# ArtFire.net
KiCad netlist of a schematic drawn in Altium Designer
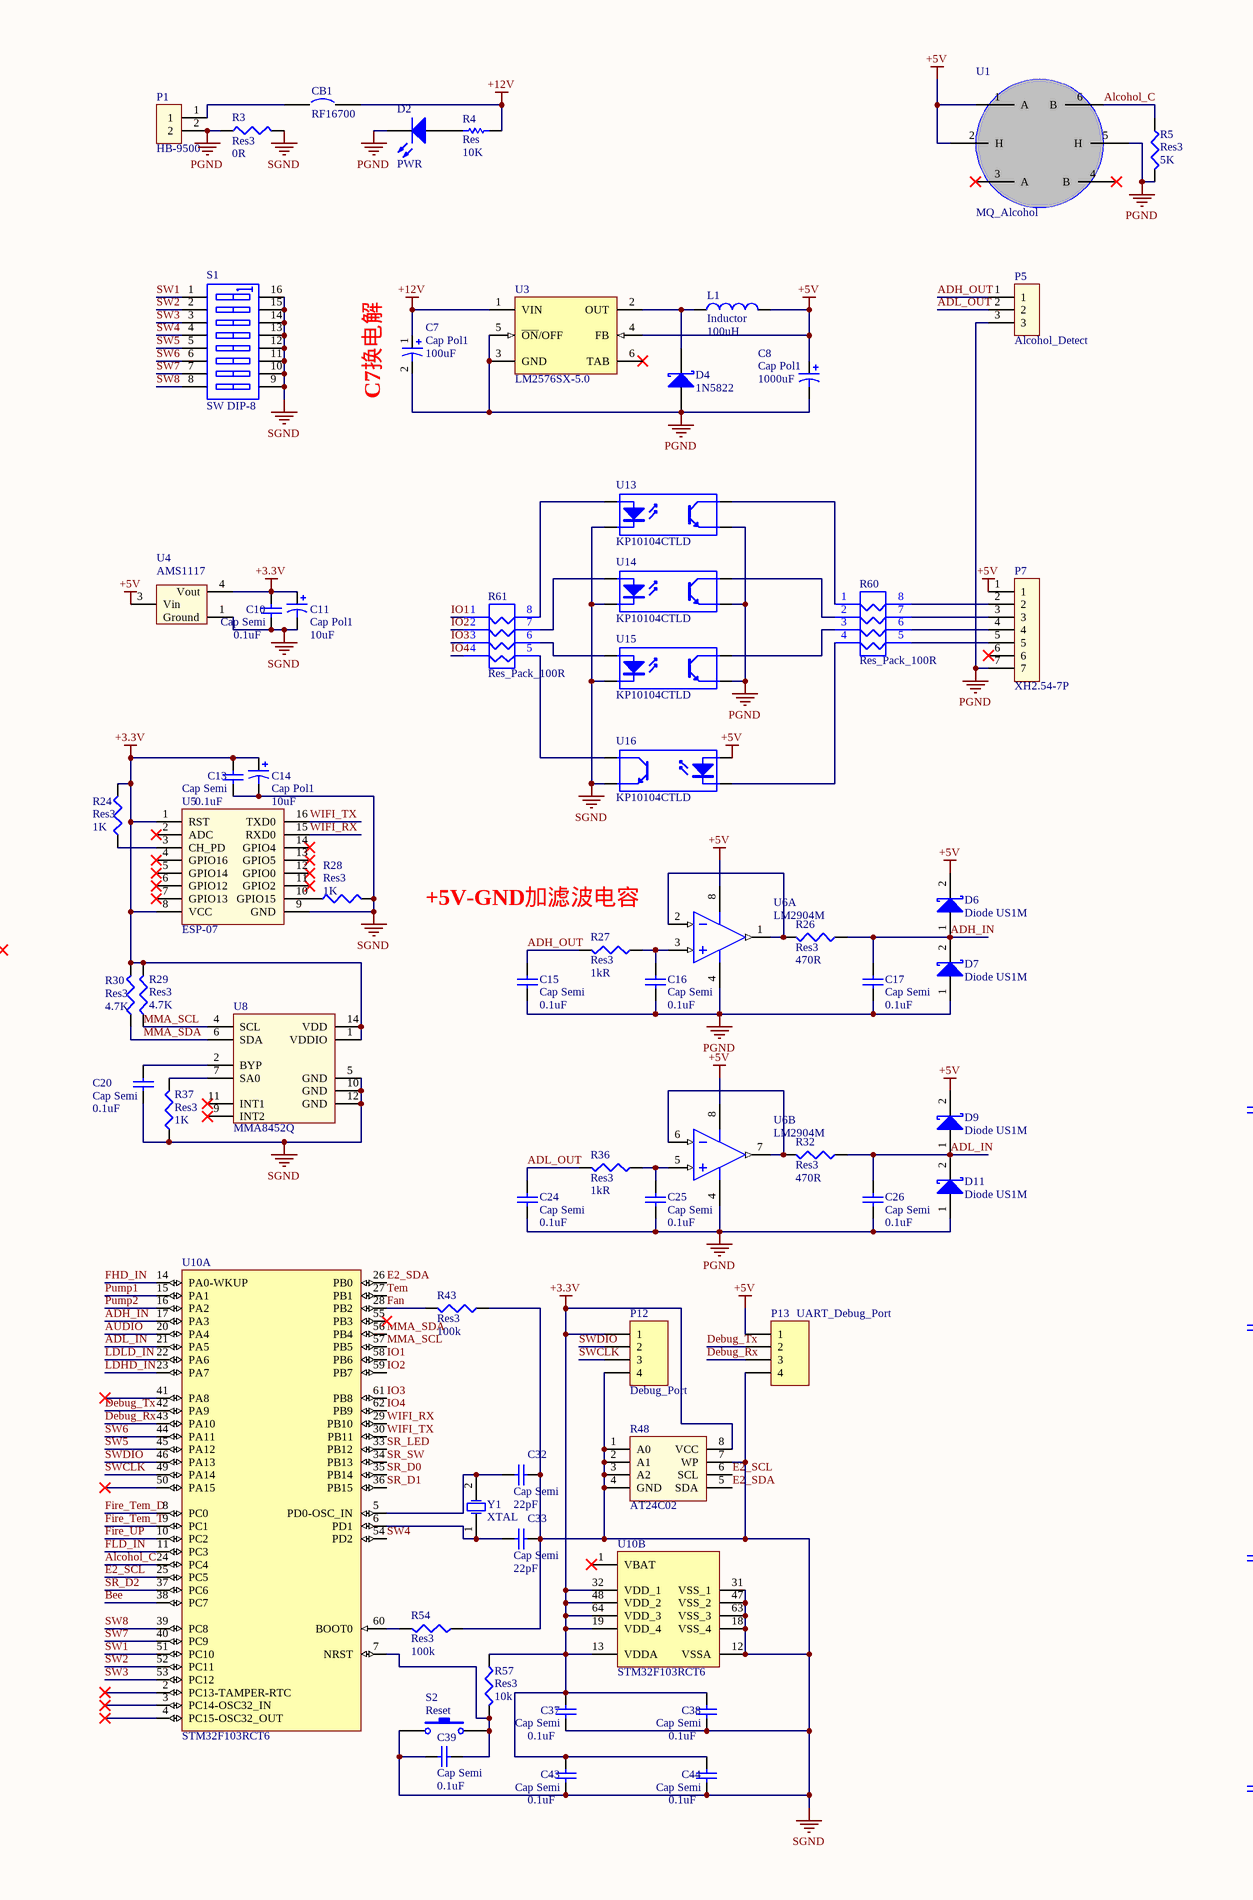
[diagram p0: ArtFire.SchDoc, left]
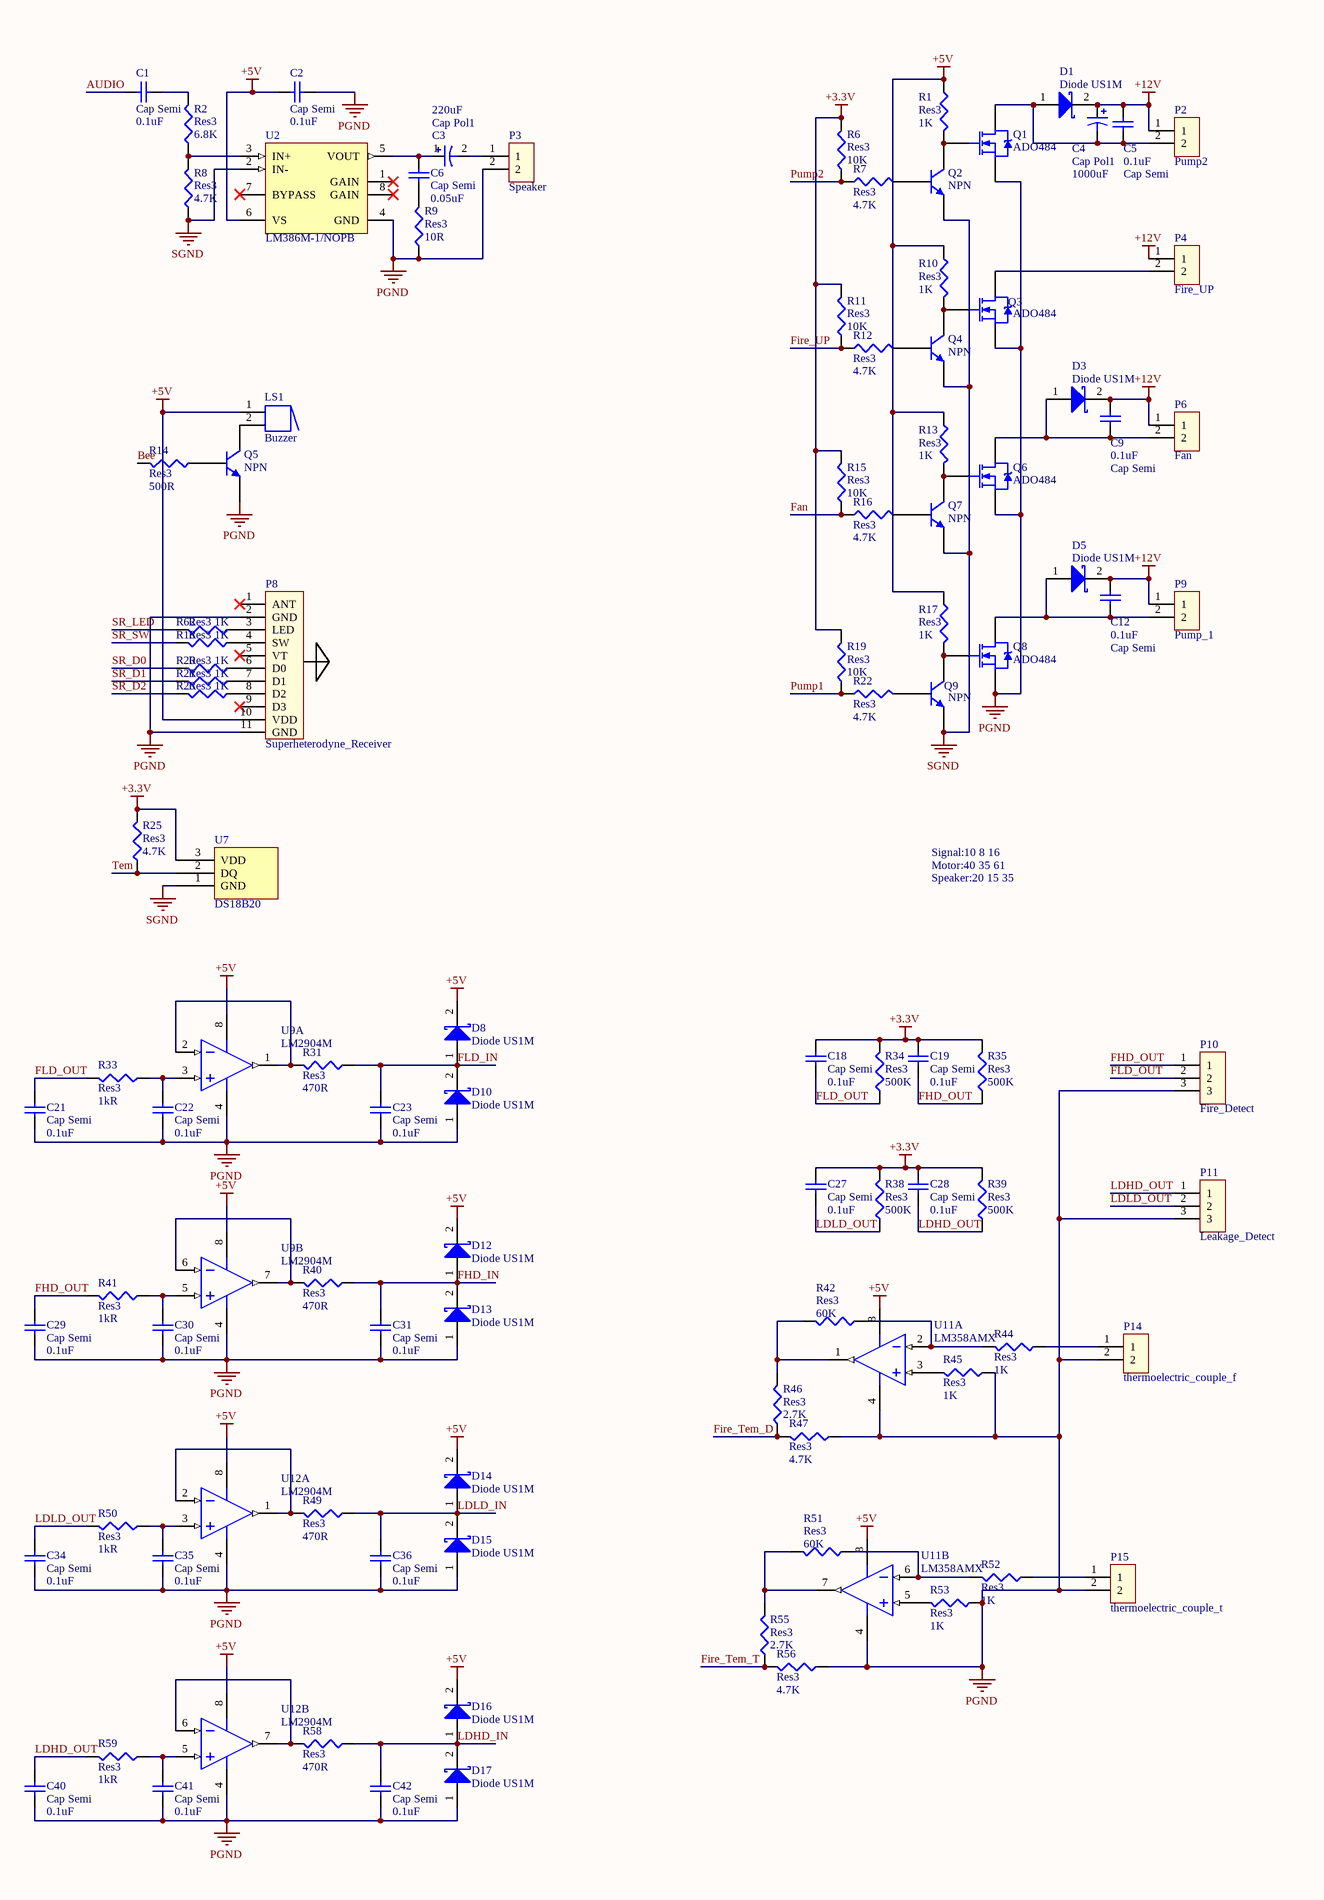
[diagram p1: ArtFire.SchDoc, right]

(export (version "E")
  (design (tool "Eeschema 10.0.6"))
  (components
    (comp (ref "C1")
      (value "Cap Semi")
      (footprint "6-0805_N")
      (description "Capacitor (Semiconductor SIM Model)")
      (fields (field (name "ALTIUM_VALUE") "0.1uF") (field (name "PUBLISHER") "Altium Limited"))
      (libsource (lib "Miscellaneous Devices") (part "Cap Semi"))
    )
    (comp (ref "C2")
      (value "Cap Semi")
      (footprint "6-0805_N")
      (description "Capacitor (Semiconductor SIM Model)")
      (fields (field (name "ALTIUM_VALUE") "0.1uF") (field (name "PUBLISHER") "Altium Limited"))
      (libsource (lib "Miscellaneous Devices") (part "Cap Semi"))
    )
    (comp (ref "C3")
      (value "Cap Pol1")
      (footprint "CAP_6.3*5.4MM")
      (description "Polarized Capacitor (Radial)")
      (fields (field (name "ALTIUM_VALUE") "220uF") (field (name "PUBLISHER") "Altium Limited"))
      (libsource (lib "Miscellaneous Devices") (part "Cap Pol1"))
    )
    (comp (ref "C4")
      (value "Cap Pol1")
      (footprint "CAP_10*10MM")
      (description "Polarized Capacitor (Radial)")
      (fields (field (name "ALTIUM_VALUE") "1000uF") (field (name "PUBLISHER") "Altium Limited"))
      (libsource (lib "") (part "Cap Pol1_1"))
    )
    (comp (ref "C5")
      (value "Cap Semi")
      (footprint "6-0805_N")
      (description "Capacitor (Semiconductor SIM Model)")
      (fields (field (name "ALTIUM_VALUE") "0.1uF") (field (name "PUBLISHER") "Altium Limited"))
      (libsource (lib "Miscellaneous Devices") (part "Cap Semi"))
    )
    (comp (ref "C6")
      (value "Cap Semi")
      (footprint "6-0805_N")
      (description "Capacitor (Semiconductor SIM Model)")
      (fields (field (name "ALTIUM_VALUE") "0.05uF") (field (name "PUBLISHER") "Altium Limited"))
      (libsource (lib "Miscellaneous Devices") (part "Cap Semi"))
    )
    (comp (ref "C7")
      (value "Cap Pol1")
      (footprint "6032")
      (description "Polarized Capacitor (Radial)")
      (fields (field (name "ALTIUM_VALUE") "100uF") (field (name "PUBLISHER") "Altium Limited"))
      (libsource (lib "Miscellaneous Devices") (part "Cap Pol1"))
    )
    (comp (ref "C8")
      (value "Cap Pol1")
      (footprint "CAP_10*10MM")
      (description "Polarized Capacitor (Radial)")
      (fields (field (name "ALTIUM_VALUE") "1000uF") (field (name "PUBLISHER") "Altium Limited"))
      (libsource (lib "") (part "Cap Pol1_1"))
    )
    (comp (ref "C9")
      (value "Cap Semi")
      (footprint "6-0805_N")
      (description "Capacitor (Semiconductor SIM Model)")
      (fields (field (name "ALTIUM_VALUE") "0.1uF") (field (name "PUBLISHER") "Altium Limited"))
      (libsource (lib "Miscellaneous Devices") (part "Cap Semi"))
    )
    (comp (ref "C10")
      (value "Cap Semi")
      (footprint "6-0805_N")
      (description "Capacitor (Semiconductor SIM Model)")
      (fields (field (name "ALTIUM_VALUE") "0.1uF") (field (name "PUBLISHER") "Altium Limited"))
      (libsource (lib "Miscellaneous Devices") (part "Cap Semi"))
    )
    (comp (ref "C11")
      (value "Cap Pol1")
      (footprint "Cap_5*4mm")
      (description "Polarized Capacitor (Radial)")
      (fields (field (name "ALTIUM_VALUE") "10uF") (field (name "PUBLISHER") "Altium Limited"))
      (libsource (lib "") (part "Cap Pol1_1"))
    )
    (comp (ref "C12")
      (value "Cap Semi")
      (footprint "6-0805_N")
      (description "Capacitor (Semiconductor SIM Model)")
      (fields (field (name "ALTIUM_VALUE") "0.1uF") (field (name "PUBLISHER") "Altium Limited"))
      (libsource (lib "Miscellaneous Devices") (part "Cap Semi"))
    )
    (comp (ref "C13")
      (value "Cap Semi")
      (footprint "6-0805_N")
      (description "Capacitor (Semiconductor SIM Model)")
      (fields (field (name "ALTIUM_VALUE") "0.1uF") (field (name "PUBLISHER") "Altium Limited"))
      (libsource (lib "Miscellaneous Devices") (part "Cap Semi"))
    )
    (comp (ref "C14")
      (value "Cap Pol1")
      (footprint "Cap_5*4mm")
      (description "Polarized Capacitor (Radial)")
      (fields (field (name "ALTIUM_VALUE") "10uF") (field (name "PUBLISHER") "Altium Limited"))
      (libsource (lib "") (part "Cap Pol1_1"))
    )
    (comp (ref "C15")
      (value "Cap Semi")
      (footprint "6-0805_N")
      (description "Capacitor (Semiconductor SIM Model)")
      (fields (field (name "ALTIUM_VALUE") "0.1uF") (field (name "PUBLISHER") "Altium Limited"))
      (libsource (lib "Miscellaneous Devices") (part "Cap Semi"))
    )
    (comp (ref "C16")
      (value "Cap Semi")
      (footprint "6-0805_N")
      (description "Capacitor (Semiconductor SIM Model)")
      (fields (field (name "ALTIUM_VALUE") "0.1uF") (field (name "PUBLISHER") "Altium Limited"))
      (libsource (lib "Miscellaneous Devices") (part "Cap Semi"))
    )
    (comp (ref "C17")
      (value "Cap Semi")
      (footprint "6-0805_N")
      (description "Capacitor (Semiconductor SIM Model)")
      (fields (field (name "ALTIUM_VALUE") "0.1uF") (field (name "PUBLISHER") "Altium Limited"))
      (libsource (lib "Miscellaneous Devices") (part "Cap Semi"))
    )
    (comp (ref "C18")
      (value "Cap Semi")
      (footprint "6-0805_N")
      (description "Capacitor (Semiconductor SIM Model)")
      (fields (field (name "ALTIUM_VALUE") "0.1uF") (field (name "PUBLISHER") "Altium Limited"))
      (libsource (lib "Miscellaneous Devices") (part "Cap Semi"))
    )
    (comp (ref "C19")
      (value "Cap Semi")
      (footprint "6-0805_N")
      (description "Capacitor (Semiconductor SIM Model)")
      (fields (field (name "ALTIUM_VALUE") "0.1uF") (field (name "PUBLISHER") "Altium Limited"))
      (libsource (lib "Miscellaneous Devices") (part "Cap Semi"))
    )
    (comp (ref "C20")
      (value "Cap Semi")
      (footprint "6-0805_N")
      (description "Capacitor (Semiconductor SIM Model)")
      (fields (field (name "ALTIUM_VALUE") "0.1uF") (field (name "PUBLISHER") "Altium Limited"))
      (libsource (lib "Miscellaneous Devices") (part "Cap Semi"))
    )
    (comp (ref "C21")
      (value "Cap Semi")
      (footprint "6-0805_N")
      (description "Capacitor (Semiconductor SIM Model)")
      (fields (field (name "ALTIUM_VALUE") "0.1uF") (field (name "PUBLISHER") "Altium Limited"))
      (libsource (lib "Miscellaneous Devices") (part "Cap Semi"))
    )
    (comp (ref "C22")
      (value "Cap Semi")
      (footprint "6-0805_N")
      (description "Capacitor (Semiconductor SIM Model)")
      (fields (field (name "ALTIUM_VALUE") "0.1uF") (field (name "PUBLISHER") "Altium Limited"))
      (libsource (lib "Miscellaneous Devices") (part "Cap Semi"))
    )
    (comp (ref "C23")
      (value "Cap Semi")
      (footprint "6-0805_N")
      (description "Capacitor (Semiconductor SIM Model)")
      (fields (field (name "ALTIUM_VALUE") "0.1uF") (field (name "PUBLISHER") "Altium Limited"))
      (libsource (lib "Miscellaneous Devices") (part "Cap Semi"))
    )
    (comp (ref "C24")
      (value "Cap Semi")
      (footprint "6-0805_N")
      (description "Capacitor (Semiconductor SIM Model)")
      (fields (field (name "ALTIUM_VALUE") "0.1uF") (field (name "PUBLISHER") "Altium Limited"))
      (libsource (lib "Miscellaneous Devices") (part "Cap Semi"))
    )
    (comp (ref "C25")
      (value "Cap Semi")
      (footprint "6-0805_N")
      (description "Capacitor (Semiconductor SIM Model)")
      (fields (field (name "ALTIUM_VALUE") "0.1uF") (field (name "PUBLISHER") "Altium Limited"))
      (libsource (lib "Miscellaneous Devices") (part "Cap Semi"))
    )
    (comp (ref "C26")
      (value "Cap Semi")
      (footprint "6-0805_N")
      (description "Capacitor (Semiconductor SIM Model)")
      (fields (field (name "ALTIUM_VALUE") "0.1uF") (field (name "PUBLISHER") "Altium Limited"))
      (libsource (lib "Miscellaneous Devices") (part "Cap Semi"))
    )
    (comp (ref "C27")
      (value "Cap Semi")
      (footprint "6-0805_N")
      (description "Capacitor (Semiconductor SIM Model)")
      (fields (field (name "ALTIUM_VALUE") "0.1uF") (field (name "PUBLISHER") "Altium Limited"))
      (libsource (lib "Miscellaneous Devices") (part "Cap Semi"))
    )
    (comp (ref "C28")
      (value "Cap Semi")
      (footprint "6-0805_N")
      (description "Capacitor (Semiconductor SIM Model)")
      (fields (field (name "ALTIUM_VALUE") "0.1uF") (field (name "PUBLISHER") "Altium Limited"))
      (libsource (lib "Miscellaneous Devices") (part "Cap Semi"))
    )
    (comp (ref "C29")
      (value "Cap Semi")
      (footprint "6-0805_N")
      (description "Capacitor (Semiconductor SIM Model)")
      (fields (field (name "ALTIUM_VALUE") "0.1uF") (field (name "PUBLISHER") "Altium Limited"))
      (libsource (lib "Miscellaneous Devices") (part "Cap Semi"))
    )
    (comp (ref "C30")
      (value "Cap Semi")
      (footprint "6-0805_N")
      (description "Capacitor (Semiconductor SIM Model)")
      (fields (field (name "ALTIUM_VALUE") "0.1uF") (field (name "PUBLISHER") "Altium Limited"))
      (libsource (lib "Miscellaneous Devices") (part "Cap Semi"))
    )
    (comp (ref "C31")
      (value "Cap Semi")
      (footprint "6-0805_N")
      (description "Capacitor (Semiconductor SIM Model)")
      (fields (field (name "ALTIUM_VALUE") "0.1uF") (field (name "PUBLISHER") "Altium Limited"))
      (libsource (lib "Miscellaneous Devices") (part "Cap Semi"))
    )
    (comp (ref "C32")
      (value "Cap Semi")
      (footprint "6-0805_N")
      (description "Capacitor (Semiconductor SIM Model)")
      (fields (field (name "ALTIUM_VALUE") "22pF") (field (name "PUBLISHER") "Altium Limited"))
      (libsource (lib "Miscellaneous Devices") (part "Cap Semi"))
    )
    (comp (ref "C33")
      (value "Cap Semi")
      (footprint "6-0805_N")
      (description "Capacitor (Semiconductor SIM Model)")
      (fields (field (name "ALTIUM_VALUE") "22pF") (field (name "PUBLISHER") "Altium Limited"))
      (libsource (lib "Miscellaneous Devices") (part "Cap Semi"))
    )
    (comp (ref "C34")
      (value "Cap Semi")
      (footprint "6-0805_N")
      (description "Capacitor (Semiconductor SIM Model)")
      (fields (field (name "ALTIUM_VALUE") "0.1uF") (field (name "PUBLISHER") "Altium Limited"))
      (libsource (lib "Miscellaneous Devices") (part "Cap Semi"))
    )
    (comp (ref "C35")
      (value "Cap Semi")
      (footprint "6-0805_N")
      (description "Capacitor (Semiconductor SIM Model)")
      (fields (field (name "ALTIUM_VALUE") "0.1uF") (field (name "PUBLISHER") "Altium Limited"))
      (libsource (lib "Miscellaneous Devices") (part "Cap Semi"))
    )
    (comp (ref "C36")
      (value "Cap Semi")
      (footprint "6-0805_N")
      (description "Capacitor (Semiconductor SIM Model)")
      (fields (field (name "ALTIUM_VALUE") "0.1uF") (field (name "PUBLISHER") "Altium Limited"))
      (libsource (lib "Miscellaneous Devices") (part "Cap Semi"))
    )
    (comp (ref "C37")
      (value "Cap Semi")
      (footprint "6-0805_N")
      (description "Capacitor (Semiconductor SIM Model)")
      (fields (field (name "ALTIUM_VALUE") "0.1uF") (field (name "PUBLISHER") "Altium Limited"))
      (libsource (lib "Miscellaneous Devices") (part "Cap Semi"))
    )
    (comp (ref "C38")
      (value "Cap Semi")
      (footprint "6-0805_N")
      (description "Capacitor (Semiconductor SIM Model)")
      (fields (field (name "ALTIUM_VALUE") "0.1uF") (field (name "PUBLISHER") "Altium Limited"))
      (libsource (lib "Miscellaneous Devices") (part "Cap Semi"))
    )
    (comp (ref "C39")
      (value "Cap Semi")
      (footprint "6-0805_N")
      (description "Capacitor (Semiconductor SIM Model)")
      (fields (field (name "ALTIUM_VALUE") "0.1uF") (field (name "PUBLISHER") "Altium Limited"))
      (libsource (lib "Miscellaneous Devices") (part "Cap Semi"))
    )
    (comp (ref "C40")
      (value "Cap Semi")
      (footprint "6-0805_N")
      (description "Capacitor (Semiconductor SIM Model)")
      (fields (field (name "ALTIUM_VALUE") "0.1uF") (field (name "PUBLISHER") "Altium Limited"))
      (libsource (lib "Miscellaneous Devices") (part "Cap Semi"))
    )
    (comp (ref "C41")
      (value "Cap Semi")
      (footprint "6-0805_N")
      (description "Capacitor (Semiconductor SIM Model)")
      (fields (field (name "ALTIUM_VALUE") "0.1uF") (field (name "PUBLISHER") "Altium Limited"))
      (libsource (lib "Miscellaneous Devices") (part "Cap Semi"))
    )
    (comp (ref "C42")
      (value "Cap Semi")
      (footprint "6-0805_N")
      (description "Capacitor (Semiconductor SIM Model)")
      (fields (field (name "ALTIUM_VALUE") "0.1uF") (field (name "PUBLISHER") "Altium Limited"))
      (libsource (lib "Miscellaneous Devices") (part "Cap Semi"))
    )
    (comp (ref "C43")
      (value "Cap Semi")
      (footprint "6-0805_N")
      (description "Capacitor (Semiconductor SIM Model)")
      (fields (field (name "ALTIUM_VALUE") "0.1uF") (field (name "PUBLISHER") "Altium Limited"))
      (libsource (lib "Miscellaneous Devices") (part "Cap Semi"))
    )
    (comp (ref "C44")
      (value "Cap Semi")
      (footprint "6-0805_N")
      (description "Capacitor (Semiconductor SIM Model)")
      (fields (field (name "ALTIUM_VALUE") "0.1uF") (field (name "PUBLISHER") "Altium Limited"))
      (libsource (lib "Miscellaneous Devices") (part "Cap Semi"))
    )
    (comp (ref "CB1")
      (value "RF16700")
      (footprint "SPST-2")
      (description "Circuit Breaker")
      (fields (field (name "PUBLISHER") "Altium Limited"))
      (libsource (lib "Miscellaneous Devices") (part "Circuit Breaker"))
    )
    (comp (ref "D1")
      (value "Diode US1M")
      (footprint "US1M")
      (description "Silicon RF Schottky Diode for Mixer Applications in the VHF/UHF Range")
      (fields (field (name "PUBLISHER") "Altium Limited"))
      (libsource (lib "Miscellaneous Devices") (part "Diode BAT17"))
    )
    (comp (ref "D2")
      (value "PWR")
      (footprint "6-0805_N")
      (description "Typical INFRARED GaAs LED")
      (fields (field (name "PUBLISHER") "Altium Limited"))
      (libsource (lib "Miscellaneous Devices") (part "LED0"))
    )
    (comp (ref "D3")
      (value "Diode US1M")
      (footprint "US1M")
      (description "Silicon RF Schottky Diode for Mixer Applications in the VHF/UHF Range")
      (fields (field (name "PUBLISHER") "Altium Limited"))
      (libsource (lib "Miscellaneous Devices") (part "Diode BAT17"))
    )
    (comp (ref "D4")
      (value "1N5822")
      (footprint "US1M")
      (description "Silicon RF Schottky Diode for Mixer Applications in the VHF/UHF Range")
      (fields (field (name "PUBLISHER") "Altium Limited"))
      (libsource (lib "") (part "Diode BAT17_1"))
    )
    (comp (ref "D5")
      (value "Diode US1M")
      (footprint "US1M")
      (description "Silicon RF Schottky Diode for Mixer Applications in the VHF/UHF Range")
      (fields (field (name "PUBLISHER") "Altium Limited"))
      (libsource (lib "Miscellaneous Devices") (part "Diode BAT17"))
    )
    (comp (ref "D6")
      (value "Diode US1M")
      (footprint "US1M")
      (description "Silicon RF Schottky Diode for Mixer Applications in the VHF/UHF Range")
      (fields (field (name "PUBLISHER") "Altium Limited"))
      (libsource (lib "Miscellaneous Devices") (part "Diode BAT17"))
    )
    (comp (ref "D7")
      (value "Diode US1M")
      (footprint "US1M")
      (description "Silicon RF Schottky Diode for Mixer Applications in the VHF/UHF Range")
      (fields (field (name "PUBLISHER") "Altium Limited"))
      (libsource (lib "Miscellaneous Devices") (part "Diode BAT17"))
    )
    (comp (ref "D8")
      (value "Diode US1M")
      (footprint "US1M")
      (description "Silicon RF Schottky Diode for Mixer Applications in the VHF/UHF Range")
      (fields (field (name "PUBLISHER") "Altium Limited"))
      (libsource (lib "Miscellaneous Devices") (part "Diode BAT17"))
    )
    (comp (ref "D9")
      (value "Diode US1M")
      (footprint "US1M")
      (description "Silicon RF Schottky Diode for Mixer Applications in the VHF/UHF Range")
      (fields (field (name "PUBLISHER") "Altium Limited"))
      (libsource (lib "Miscellaneous Devices") (part "Diode BAT17"))
    )
    (comp (ref "D10")
      (value "Diode US1M")
      (footprint "US1M")
      (description "Silicon RF Schottky Diode for Mixer Applications in the VHF/UHF Range")
      (fields (field (name "PUBLISHER") "Altium Limited"))
      (libsource (lib "Miscellaneous Devices") (part "Diode BAT17"))
    )
    (comp (ref "D11")
      (value "Diode US1M")
      (footprint "US1M")
      (description "Silicon RF Schottky Diode for Mixer Applications in the VHF/UHF Range")
      (fields (field (name "PUBLISHER") "Altium Limited"))
      (libsource (lib "Miscellaneous Devices") (part "Diode BAT17"))
    )
    (comp (ref "D12")
      (value "Diode US1M")
      (footprint "US1M")
      (description "Silicon RF Schottky Diode for Mixer Applications in the VHF/UHF Range")
      (fields (field (name "PUBLISHER") "Altium Limited"))
      (libsource (lib "Miscellaneous Devices") (part "Diode BAT17"))
    )
    (comp (ref "D13")
      (value "Diode US1M")
      (footprint "US1M")
      (description "Silicon RF Schottky Diode for Mixer Applications in the VHF/UHF Range")
      (fields (field (name "PUBLISHER") "Altium Limited"))
      (libsource (lib "Miscellaneous Devices") (part "Diode BAT17"))
    )
    (comp (ref "D14")
      (value "Diode US1M")
      (footprint "US1M")
      (description "Silicon RF Schottky Diode for Mixer Applications in the VHF/UHF Range")
      (fields (field (name "PUBLISHER") "Altium Limited"))
      (libsource (lib "Miscellaneous Devices") (part "Diode BAT17"))
    )
    (comp (ref "D15")
      (value "Diode US1M")
      (footprint "US1M")
      (description "Silicon RF Schottky Diode for Mixer Applications in the VHF/UHF Range")
      (fields (field (name "PUBLISHER") "Altium Limited"))
      (libsource (lib "Miscellaneous Devices") (part "Diode BAT17"))
    )
    (comp (ref "D16")
      (value "Diode US1M")
      (footprint "US1M")
      (description "Silicon RF Schottky Diode for Mixer Applications in the VHF/UHF Range")
      (fields (field (name "PUBLISHER") "Altium Limited"))
      (libsource (lib "Miscellaneous Devices") (part "Diode BAT17"))
    )
    (comp (ref "D17")
      (value "Diode US1M")
      (footprint "US1M")
      (description "Silicon RF Schottky Diode for Mixer Applications in the VHF/UHF Range")
      (fields (field (name "PUBLISHER") "Altium Limited"))
      (libsource (lib "Miscellaneous Devices") (part "Diode BAT17"))
    )
    (comp (ref "L1")
      (value "Inductor")
      (footprint "CDRH127")
      (fields (field (name "ALTIUM_VALUE") "100uH") (field (name "PUBLISHER") "Altium Limited"))
      (libsource (lib "Miscellaneous Devices") (part "Inductor"))
    )
    (comp (ref "LS1")
      (value "Buzzer")
      (footprint "BUZZER")
      (description "Magnetic Transducer Buzzer")
      (fields (field (name "PUBLISHER") "Altium Limited"))
      (libsource (lib "Miscellaneous Devices") (part "Buzzer"))
    )
    (comp (ref "P1")
      (value "HB-9500")
      (footprint "HB-9500")
      (description "High current connector")
      (libsource (lib "Simon'Library") (part "HB-9500"))
    )
    (comp (ref "P2") (value "Pump2") (footprint "CH3.96_2P") (libsource (lib "CH3.96") (part "CH3.96_2P")))
    (comp (ref "P3") (value "Speaker") (footprint "XH2.54-2P") (libsource (lib "XH2.54") (part "XH2.54-2P")))
    (comp (ref "P4") (value "Fire_UP") (footprint "KF7.62-2P") (libsource (lib "KF3.96") (part "KF3.96")))
    (comp (ref "P5")
      (value "Alcohol_Detect")
      (footprint "XH2.54-3P")
      (libsource (lib "XH2.54") (part "XH2.54-3P"))
    )
    (comp (ref "P6") (value "Fan") (footprint "XH2.54-2P") (libsource (lib "XH2.54") (part "XH2.54-2P")))
    (comp (ref "P7")
      (value "XH2.54-7P")
      (footprint "XH2.54-7P")
      (libsource (lib "XH2.54") (part "XH2.54-7P"))
    )
    (comp (ref "P8")
      (value "Superheterodyne_Receiver")
      (footprint "Sperheterodyne_Receiver")
      (libsource (lib "Simon'Library") (part "Superheterodyne_Receiver"))
    )
    (comp (ref "P9") (value "Pump_1") (footprint "CH3.96_2P") (libsource (lib "CH3.96") (part "CH3.96_2P")))
    (comp (ref "P10")
      (value "Fire_Detect")
      (footprint "CH3.96_3P")
      (libsource (lib "CH3.96") (part "CH3.96_3P"))
    )
    (comp (ref "P11")
      (value "Leakage_Detect")
      (footprint "XH2.54-3P")
      (libsource (lib "XH2.54") (part "XH2.54-3P"))
    )
    (comp (ref "P12")
      (value "Debug_Port")
      (footprint "HDR1X4")
      (description "Header, 4-Pin")
      (fields (field (name "PUBLISHER") "Altium Limited"))
      (libsource (lib "Miscellaneous Connectors") (part "Header 4"))
    )
    (comp (ref "P13")
      (value "UART_Debug_Port")
      (footprint "HDR1X4")
      (description "Header, 4-Pin")
      (fields (field (name "PUBLISHER") "Altium Limited"))
      (libsource (lib "Miscellaneous Connectors") (part "Header 4"))
    )
    (comp (ref "P14")
      (value "thermoelectric_couple_f")
      (footprint "KF7.62-2P")
      (libsource (lib "KF3.96") (part "KF3.96"))
    )
    (comp (ref "P15")
      (value "thermoelectric_couple_t")
      (footprint "KF7.62-2P")
      (libsource (lib "KF3.96") (part "KF3.96"))
    )
    (comp (ref "Q1")
      (value "ADO484")
      (footprint "DPAK_AOD484")
      (description "N-Channel Power MOSFET")
      (fields (field (name "PUBLISHER") "Altium Limited"))
      (libsource (lib "Miscellaneous Devices") (part "NMOS-2"))
    )
    (comp (ref "Q2")
      (value "NPN")
      (footprint "SOT-23_N")
      (description "NPN Bipolar Transistor")
      (fields (field (name "PUBLISHER") "Altium Limited"))
      (libsource (lib "Miscellaneous Devices") (part "NPN"))
    )
    (comp (ref "Q3")
      (value "ADO484")
      (footprint "DPAK_AOD484")
      (description "N-Channel Power MOSFET")
      (fields (field (name "PUBLISHER") "Altium Limited"))
      (libsource (lib "Miscellaneous Devices") (part "NMOS-2"))
    )
    (comp (ref "Q4")
      (value "NPN")
      (footprint "SOT-23_N")
      (description "NPN Bipolar Transistor")
      (fields (field (name "PUBLISHER") "Altium Limited"))
      (libsource (lib "Miscellaneous Devices") (part "NPN"))
    )
    (comp (ref "Q5")
      (value "NPN")
      (footprint "SOT-23_N")
      (description "NPN Bipolar Transistor")
      (fields (field (name "PUBLISHER") "Altium Limited"))
      (libsource (lib "Miscellaneous Devices") (part "NPN"))
    )
    (comp (ref "Q6")
      (value "ADO484")
      (footprint "DPAK_AOD484")
      (description "N-Channel Power MOSFET")
      (fields (field (name "PUBLISHER") "Altium Limited"))
      (libsource (lib "Miscellaneous Devices") (part "NMOS-2"))
    )
    (comp (ref "Q7")
      (value "NPN")
      (footprint "SOT-23_N")
      (description "NPN Bipolar Transistor")
      (fields (field (name "PUBLISHER") "Altium Limited"))
      (libsource (lib "Miscellaneous Devices") (part "NPN"))
    )
    (comp (ref "Q8")
      (value "ADO484")
      (footprint "DPAK_AOD484")
      (description "N-Channel Power MOSFET")
      (fields (field (name "PUBLISHER") "Altium Limited"))
      (libsource (lib "Miscellaneous Devices") (part "NMOS-2"))
    )
    (comp (ref "Q9")
      (value "NPN")
      (footprint "SOT-23_N")
      (description "NPN Bipolar Transistor")
      (fields (field (name "PUBLISHER") "Altium Limited"))
      (libsource (lib "Miscellaneous Devices") (part "NPN"))
    )
    (comp (ref "R1")
      (value "Res3")
      (footprint "6-0805_N")
      (description "Resistor")
      (fields (field (name "ALTIUM_VALUE") "1K") (field (name "PUBLISHER") "Altium Limited"))
      (libsource (lib "Miscellaneous Devices") (part "Res3"))
    )
    (comp (ref "R2")
      (value "Res3")
      (footprint "6-0805_N")
      (description "Resistor")
      (fields (field (name "ALTIUM_VALUE") "6.8K") (field (name "PUBLISHER") "Altium Limited"))
      (libsource (lib "Miscellaneous Devices") (part "Res3"))
    )
    (comp (ref "R3")
      (value "Res3")
      (footprint "6-0805_N")
      (description "Resistor")
      (fields (field (name "ALTIUM_VALUE") "0R") (field (name "PUBLISHER") "Altium Limited"))
      (libsource (lib "Miscellaneous Devices") (part "Res3"))
    )
    (comp (ref "R4")
      (value "Res")
      (footprint "6-0805_N")
      (description "Resistor")
      (fields (field (name "ALTIUM_VALUE") "10K") (field (name "PUBLISHER") "Altium Limited"))
      (libsource (lib "Miscellaneous Devices") (part "Res1"))
    )
    (comp (ref "R5")
      (value "Res3")
      (footprint "6-0805_N")
      (description "Resistor")
      (fields (field (name "ALTIUM_VALUE") "5K") (field (name "PUBLISHER") "Altium Limited"))
      (libsource (lib "Miscellaneous Devices") (part "Res3"))
    )
    (comp (ref "R6")
      (value "Res3")
      (footprint "6-0805_N")
      (description "Resistor")
      (fields (field (name "ALTIUM_VALUE") "10K") (field (name "PUBLISHER") "Altium Limited"))
      (libsource (lib "Miscellaneous Devices") (part "Res3"))
    )
    (comp (ref "R7")
      (value "Res3")
      (footprint "6-0805_N")
      (description "Resistor")
      (fields (field (name "ALTIUM_VALUE") "4.7K") (field (name "PUBLISHER") "Altium Limited"))
      (libsource (lib "Miscellaneous Devices") (part "Res3"))
    )
    (comp (ref "R8")
      (value "Res3")
      (footprint "6-0805_N")
      (description "Resistor")
      (fields (field (name "ALTIUM_VALUE") "4.7K") (field (name "PUBLISHER") "Altium Limited"))
      (libsource (lib "Miscellaneous Devices") (part "Res3"))
    )
    (comp (ref "R9")
      (value "Res3")
      (footprint "6-0805_N")
      (description "Resistor")
      (fields (field (name "ALTIUM_VALUE") "10R") (field (name "PUBLISHER") "Altium Limited"))
      (libsource (lib "Miscellaneous Devices") (part "Res3"))
    )
    (comp (ref "R10")
      (value "Res3")
      (footprint "6-0805_N")
      (description "Resistor")
      (fields (field (name "ALTIUM_VALUE") "1K") (field (name "PUBLISHER") "Altium Limited"))
      (libsource (lib "Miscellaneous Devices") (part "Res3"))
    )
    (comp (ref "R11")
      (value "Res3")
      (footprint "6-0805_N")
      (description "Resistor")
      (fields (field (name "ALTIUM_VALUE") "10K") (field (name "PUBLISHER") "Altium Limited"))
      (libsource (lib "Miscellaneous Devices") (part "Res3"))
    )
    (comp (ref "R12")
      (value "Res3")
      (footprint "6-0805_N")
      (description "Resistor")
      (fields (field (name "ALTIUM_VALUE") "4.7K") (field (name "PUBLISHER") "Altium Limited"))
      (libsource (lib "Miscellaneous Devices") (part "Res3"))
    )
    (comp (ref "R13")
      (value "Res3")
      (footprint "6-0805_N")
      (description "Resistor")
      (fields (field (name "ALTIUM_VALUE") "1K") (field (name "PUBLISHER") "Altium Limited"))
      (libsource (lib "Miscellaneous Devices") (part "Res3"))
    )
    (comp (ref "R14")
      (value "Res3")
      (footprint "6-0805_N")
      (description "Resistor")
      (fields (field (name "ALTIUM_VALUE") "500R") (field (name "PUBLISHER") "Altium Limited"))
      (libsource (lib "Miscellaneous Devices") (part "Res3"))
    )
    (comp (ref "R15")
      (value "Res3")
      (footprint "6-0805_N")
      (description "Resistor")
      (fields (field (name "ALTIUM_VALUE") "10K") (field (name "PUBLISHER") "Altium Limited"))
      (libsource (lib "Miscellaneous Devices") (part "Res3"))
    )
    (comp (ref "R16")
      (value "Res3")
      (footprint "6-0805_N")
      (description "Resistor")
      (fields (field (name "ALTIUM_VALUE") "4.7K") (field (name "PUBLISHER") "Altium Limited"))
      (libsource (lib "Miscellaneous Devices") (part "Res3"))
    )
    (comp (ref "R17")
      (value "Res3")
      (footprint "6-0805_N")
      (description "Resistor")
      (fields (field (name "ALTIUM_VALUE") "1K") (field (name "PUBLISHER") "Altium Limited"))
      (libsource (lib "Miscellaneous Devices") (part "Res3"))
    )
    (comp (ref "R18")
      (value "Res3")
      (footprint "6-0805_N")
      (description "Resistor")
      (fields (field (name "ALTIUM_VALUE") "1K") (field (name "PUBLISHER") "Altium Limited"))
      (libsource (lib "Miscellaneous Devices") (part "Res3"))
    )
    (comp (ref "R19")
      (value "Res3")
      (footprint "6-0805_N")
      (description "Resistor")
      (fields (field (name "ALTIUM_VALUE") "10K") (field (name "PUBLISHER") "Altium Limited"))
      (libsource (lib "Miscellaneous Devices") (part "Res3"))
    )
    (comp (ref "R20")
      (value "Res3")
      (footprint "6-0805_N")
      (description "Resistor")
      (fields (field (name "ALTIUM_VALUE") "1K") (field (name "PUBLISHER") "Altium Limited"))
      (libsource (lib "Miscellaneous Devices") (part "Res3"))
    )
    (comp (ref "R21")
      (value "Res3")
      (footprint "6-0805_N")
      (description "Resistor")
      (fields (field (name "ALTIUM_VALUE") "1K") (field (name "PUBLISHER") "Altium Limited"))
      (libsource (lib "Miscellaneous Devices") (part "Res3"))
    )
    (comp (ref "R22")
      (value "Res3")
      (footprint "6-0805_N")
      (description "Resistor")
      (fields (field (name "ALTIUM_VALUE") "4.7K") (field (name "PUBLISHER") "Altium Limited"))
      (libsource (lib "Miscellaneous Devices") (part "Res3"))
    )
    (comp (ref "R23")
      (value "Res3")
      (footprint "6-0805_N")
      (description "Resistor")
      (fields (field (name "ALTIUM_VALUE") "1K") (field (name "PUBLISHER") "Altium Limited"))
      (libsource (lib "Miscellaneous Devices") (part "Res3"))
    )
    (comp (ref "R24")
      (value "Res3")
      (footprint "6-0805_N")
      (description "Resistor")
      (fields (field (name "ALTIUM_VALUE") "1K") (field (name "PUBLISHER") "Altium Limited"))
      (libsource (lib "Miscellaneous Devices") (part "Res3"))
    )
    (comp (ref "R25")
      (value "Res3")
      (footprint "6-0805_N")
      (description "Resistor")
      (fields (field (name "ALTIUM_VALUE") "4.7K") (field (name "PUBLISHER") "Altium Limited"))
      (libsource (lib "Miscellaneous Devices") (part "Res3"))
    )
    (comp (ref "R26")
      (value "Res3")
      (footprint "6-0805_N")
      (description "Resistor")
      (fields (field (name "ALTIUM_VALUE") "470R") (field (name "PUBLISHER") "Altium Limited"))
      (libsource (lib "Miscellaneous Devices") (part "Res3"))
    )
    (comp (ref "R27")
      (value "Res3")
      (footprint "6-0805_N")
      (description "Resistor")
      (fields (field (name "ALTIUM_VALUE") "1kR") (field (name "PUBLISHER") "Altium Limited"))
      (libsource (lib "Miscellaneous Devices") (part "Res3"))
    )
    (comp (ref "R28")
      (value "Res3")
      (footprint "6-0805_N")
      (description "Resistor")
      (fields (field (name "ALTIUM_VALUE") "1K") (field (name "PUBLISHER") "Altium Limited"))
      (libsource (lib "Miscellaneous Devices") (part "Res3"))
    )
    (comp (ref "R29")
      (value "Res3")
      (footprint "6-0805_N")
      (description "Resistor")
      (fields (field (name "ALTIUM_VALUE") "4.7K") (field (name "PUBLISHER") "Altium Limited"))
      (libsource (lib "Miscellaneous Devices") (part "Res3"))
    )
    (comp (ref "R30")
      (value "Res3")
      (footprint "6-0805_N")
      (description "Resistor")
      (fields (field (name "ALTIUM_VALUE") "4.7K") (field (name "PUBLISHER") "Altium Limited"))
      (libsource (lib "Miscellaneous Devices") (part "Res3"))
    )
    (comp (ref "R31")
      (value "Res3")
      (footprint "6-0805_N")
      (description "Resistor")
      (fields (field (name "ALTIUM_VALUE") "470R") (field (name "PUBLISHER") "Altium Limited"))
      (libsource (lib "Miscellaneous Devices") (part "Res3"))
    )
    (comp (ref "R32")
      (value "Res3")
      (footprint "6-0805_N")
      (description "Resistor")
      (fields (field (name "ALTIUM_VALUE") "470R") (field (name "PUBLISHER") "Altium Limited"))
      (libsource (lib "Miscellaneous Devices") (part "Res3"))
    )
    (comp (ref "R33")
      (value "Res3")
      (footprint "6-0805_N")
      (description "Resistor")
      (fields (field (name "ALTIUM_VALUE") "1kR") (field (name "PUBLISHER") "Altium Limited"))
      (libsource (lib "Miscellaneous Devices") (part "Res3"))
    )
    (comp (ref "R34")
      (value "Res3")
      (footprint "6-0805_N")
      (description "Resistor")
      (fields (field (name "ALTIUM_VALUE") "500K") (field (name "PUBLISHER") "Altium Limited"))
      (libsource (lib "Miscellaneous Devices") (part "Res3"))
    )
    (comp (ref "R35")
      (value "Res3")
      (footprint "6-0805_N")
      (description "Resistor")
      (fields (field (name "ALTIUM_VALUE") "500K") (field (name "PUBLISHER") "Altium Limited"))
      (libsource (lib "Miscellaneous Devices") (part "Res3"))
    )
    (comp (ref "R36")
      (value "Res3")
      (footprint "6-0805_N")
      (description "Resistor")
      (fields (field (name "ALTIUM_VALUE") "1kR") (field (name "PUBLISHER") "Altium Limited"))
      (libsource (lib "Miscellaneous Devices") (part "Res3"))
    )
    (comp (ref "R37")
      (value "Res3")
      (footprint "6-0805_N")
      (description "Resistor")
      (fields (field (name "ALTIUM_VALUE") "1K") (field (name "PUBLISHER") "Altium Limited"))
      (libsource (lib "Miscellaneous Devices") (part "Res3"))
    )
    (comp (ref "R38")
      (value "Res3")
      (footprint "6-0805_N")
      (description "Resistor")
      (fields (field (name "ALTIUM_VALUE") "500K") (field (name "PUBLISHER") "Altium Limited"))
      (libsource (lib "Miscellaneous Devices") (part "Res3"))
    )
    (comp (ref "R39")
      (value "Res3")
      (footprint "6-0805_N")
      (description "Resistor")
      (fields (field (name "ALTIUM_VALUE") "500K") (field (name "PUBLISHER") "Altium Limited"))
      (libsource (lib "Miscellaneous Devices") (part "Res3"))
    )
    (comp (ref "R40")
      (value "Res3")
      (footprint "6-0805_N")
      (description "Resistor")
      (fields (field (name "ALTIUM_VALUE") "470R") (field (name "PUBLISHER") "Altium Limited"))
      (libsource (lib "Miscellaneous Devices") (part "Res3"))
    )
    (comp (ref "R41")
      (value "Res3")
      (footprint "6-0805_N")
      (description "Resistor")
      (fields (field (name "ALTIUM_VALUE") "1kR") (field (name "PUBLISHER") "Altium Limited"))
      (libsource (lib "Miscellaneous Devices") (part "Res3"))
    )
    (comp (ref "R42")
      (value "Res3")
      (footprint "6-0805_N")
      (description "Resistor")
      (fields (field (name "ALTIUM_VALUE") "60K") (field (name "PUBLISHER") "Altium Limited"))
      (libsource (lib "Miscellaneous Devices") (part "Res3"))
    )
    (comp (ref "R43")
      (value "Res3")
      (footprint "6-0805_N")
      (description "Resistor")
      (fields (field (name "ALTIUM_VALUE") "100k") (field (name "PUBLISHER") "Altium Limited"))
      (libsource (lib "Miscellaneous Devices") (part "Res3"))
    )
    (comp (ref "R44")
      (value "Res3")
      (footprint "6-0805_N")
      (description "Resistor")
      (fields (field (name "ALTIUM_VALUE") "1K") (field (name "PUBLISHER") "Altium Limited"))
      (libsource (lib "Miscellaneous Devices") (part "Res3"))
    )
    (comp (ref "R45")
      (value "Res3")
      (footprint "6-0805_N")
      (description "Resistor")
      (fields (field (name "ALTIUM_VALUE") "1K") (field (name "PUBLISHER") "Altium Limited"))
      (libsource (lib "Miscellaneous Devices") (part "Res3"))
    )
    (comp (ref "R46")
      (value "Res3")
      (footprint "6-0805_N")
      (description "Resistor")
      (fields (field (name "ALTIUM_VALUE") "2.7K") (field (name "PUBLISHER") "Altium Limited"))
      (libsource (lib "Miscellaneous Devices") (part "Res3"))
    )
    (comp (ref "R47")
      (value "Res3")
      (footprint "6-0805_N")
      (description "Resistor")
      (fields (field (name "ALTIUM_VALUE") "4.7K") (field (name "PUBLISHER") "Altium Limited"))
      (libsource (lib "Miscellaneous Devices") (part "Res3"))
    )
    (comp (ref "R48")
      (value "AT24C02")
      (footprint "SOP8_TDA2822")
      (libsource (lib "Simon'Library") (part "AT24C02"))
    )
    (comp (ref "R49")
      (value "Res3")
      (footprint "6-0805_N")
      (description "Resistor")
      (fields (field (name "ALTIUM_VALUE") "470R") (field (name "PUBLISHER") "Altium Limited"))
      (libsource (lib "Miscellaneous Devices") (part "Res3"))
    )
    (comp (ref "R50")
      (value "Res3")
      (footprint "6-0805_N")
      (description "Resistor")
      (fields (field (name "ALTIUM_VALUE") "1kR") (field (name "PUBLISHER") "Altium Limited"))
      (libsource (lib "Miscellaneous Devices") (part "Res3"))
    )
    (comp (ref "R51")
      (value "Res3")
      (footprint "6-0805_N")
      (description "Resistor")
      (fields (field (name "ALTIUM_VALUE") "60K") (field (name "PUBLISHER") "Altium Limited"))
      (libsource (lib "Miscellaneous Devices") (part "Res3"))
    )
    (comp (ref "R52")
      (value "Res3")
      (footprint "6-0805_N")
      (description "Resistor")
      (fields (field (name "ALTIUM_VALUE") "1K") (field (name "PUBLISHER") "Altium Limited"))
      (libsource (lib "Miscellaneous Devices") (part "Res3"))
    )
    (comp (ref "R53")
      (value "Res3")
      (footprint "6-0805_N")
      (description "Resistor")
      (fields (field (name "ALTIUM_VALUE") "1K") (field (name "PUBLISHER") "Altium Limited"))
      (libsource (lib "Miscellaneous Devices") (part "Res3"))
    )
    (comp (ref "R54")
      (value "Res3")
      (footprint "6-0805_N")
      (description "Resistor")
      (fields (field (name "ALTIUM_VALUE") "100k") (field (name "PUBLISHER") "Altium Limited"))
      (libsource (lib "Miscellaneous Devices") (part "Res3"))
    )
    (comp (ref "R55")
      (value "Res3")
      (footprint "6-0805_N")
      (description "Resistor")
      (fields (field (name "ALTIUM_VALUE") "2.7K") (field (name "PUBLISHER") "Altium Limited"))
      (libsource (lib "Miscellaneous Devices") (part "Res3"))
    )
    (comp (ref "R56")
      (value "Res3")
      (footprint "6-0805_N")
      (description "Resistor")
      (fields (field (name "ALTIUM_VALUE") "4.7K") (field (name "PUBLISHER") "Altium Limited"))
      (libsource (lib "Miscellaneous Devices") (part "Res3"))
    )
    (comp (ref "R57")
      (value "Res3")
      (footprint "6-0805_N")
      (description "Resistor")
      (fields (field (name "ALTIUM_VALUE") "10k") (field (name "PUBLISHER") "Altium Limited"))
      (libsource (lib "Miscellaneous Devices") (part "Res3"))
    )
    (comp (ref "R58")
      (value "Res3")
      (footprint "6-0805_N")
      (description "Resistor")
      (fields (field (name "ALTIUM_VALUE") "470R") (field (name "PUBLISHER") "Altium Limited"))
      (libsource (lib "Miscellaneous Devices") (part "Res3"))
    )
    (comp (ref "R59")
      (value "Res3")
      (footprint "6-0805_N")
      (description "Resistor")
      (fields (field (name "ALTIUM_VALUE") "1kR") (field (name "PUBLISHER") "Altium Limited"))
      (libsource (lib "Miscellaneous Devices") (part "Res3"))
    )
    (comp (ref "R60")
      (value "Res_Pack_100R")
      (footprint "Res_Pack_0603")
      (description "Res_Pack_4")
      (libsource (lib "Simon'Library") (part "Res_Pack_4"))
    )
    (comp (ref "R61")
      (value "Res_Pack_100R")
      (footprint "Res_Pack_0603")
      (description "Res_Pack_4")
      (libsource (lib "Simon'Library") (part "Res_Pack_4"))
    )
    (comp (ref "R62")
      (value "Res3")
      (footprint "6-0805_N")
      (description "Resistor")
      (fields (field (name "ALTIUM_VALUE") "1K") (field (name "PUBLISHER") "Altium Limited"))
      (libsource (lib "Miscellaneous Devices") (part "Res3"))
    )
    (comp (ref "S1")
      (value "SW DIP-8")
      (footprint "DHN(F)_8Pin")
      (description "DIP Switch, 8 Position, SPST")
      (fields (field (name "PUBLISHER") "Altium Limited"))
      (libsource (lib "Miscellaneous Devices") (part "SW DIP-8"))
    )
    (comp (ref "S2")
      (value "Reset")
      (footprint "SWP_PB_6.5mm")
      (description "Switch")
      (fields (field (name "PUBLISHER") "Altium Limited"))
      (libsource (lib "Miscellaneous Devices") (part "SW-PB"))
    )
    (comp (ref "U1") (value "MQ_Alcohol") (footprint "MQ") (libsource (lib "Simon'Library") (part "MQ")))
    (comp (ref "U2")
      (value "LM386M-1/NOPB")
      (footprint "M08A_M")
      (description "Low Voltage Audio Power Amplifier, 8-pin Narrow SOIC, Pb-Free")
      (fields (field (name "MANUFACTURER") "National Semiconductor"))
      (libsource (lib "Altium Content Vault") (part "AMP-APA-LM386-8"))
    )
    (comp (ref "U3")
      (value "LM2576SX-5.0")
      (footprint "TS5B_L")
      (description "SIMPLE SWITCHER® 3A Step-Down Voltage Regulator, 5-pin TO-263")
      (fields (field (name "MANUFACTURER") "National Semiconductor"))
      (libsource (lib "Altium Content Vault") (part "PM-REG-LM2575HVS-12"))
    )
    (comp (ref "U4")
      (value "AMS1117")
      (footprint "SOT223_N")
      (libsource (lib "Simon'Library") (part "AMS1117"))
    )
    (comp (ref "U5")
      (value "ESP-07")
      (footprint "ESP-07_Wifi")
      (libsource (lib "Simon'Library") (part "ESP-07_Wifi"))
    )
    (comp (ref "U6")
      (value "LM2904M")
      (footprint "D0008A_M")
      (description "Low Power Dual Operational Amplifier, 8-pin Narrow SOIC")
      (fields (field (name "MANUFACTURER") "Texas Instruments"))
      (libsource (lib "Altium Content Vault") (part "AMP-OPA-LM158-8"))
    )
    (comp (ref "U7")
      (value "DS18B20")
      (footprint "TO-92A")
      (libsource (lib "Simon'Library") (part "DS18B20"))
    )
    (comp (ref "U8")
      (value "MMA8452Q")
      (footprint "QFN-16")
      (libsource (lib "Simon'Library") (part "MMA8452Q"))
    )
    (comp (ref "U9")
      (value "LM2904M")
      (footprint "D0008A_M")
      (description "Low Power Dual Operational Amplifier, 8-pin Narrow SOIC")
      (fields (field (name "MANUFACTURER") "Texas Instruments"))
      (libsource (lib "Altium Content Vault") (part "AMP-OPA-LM158-8"))
    )
    (comp (ref "U10")
      (value "STM32F103RCT6")
      (footprint "LQFP64_L")
      (libsource (lib "Altium Content Vault") (part "MC-ARM-STM32F101-SQ64"))
    )
    (comp (ref "U11")
      (value "LM358AMX")
      (footprint "M08A_M")
      (description "Low Power Dual Operational Amplifier, 8-pin Narrow SOIC")
      (fields (field (name "MANUFACTURER") "National Semiconductor"))
      (libsource (lib "Altium Content Vault") (part "AMP-OPA-LM158-8"))
    )
    (comp (ref "U12")
      (value "LM2904M")
      (footprint "D0008A_M")
      (description "Low Power Dual Operational Amplifier, 8-pin Narrow SOIC")
      (fields (field (name "MANUFACTURER") "Texas Instruments"))
      (libsource (lib "Altium Content Vault") (part "AMP-OPA-LM158-8"))
    )
    (comp (ref "U13")
      (value "KP10104CTLD")
      (footprint "KP10104CTLD")
      (description "4-Pin Phototransistor Optocoupler")
      (fields (field (name "PUBLISHER") "Altium Limited"))
      (libsource (lib "Miscellaneous Devices") (part "Optoisolator1"))
    )
    (comp (ref "U14")
      (value "KP10104CTLD")
      (footprint "KP10104CTLD")
      (description "4-Pin Phototransistor Optocoupler")
      (fields (field (name "PUBLISHER") "Altium Limited"))
      (libsource (lib "Miscellaneous Devices") (part "Optoisolator1"))
    )
    (comp (ref "U15")
      (value "KP10104CTLD")
      (footprint "KP10104CTLD")
      (description "4-Pin Phototransistor Optocoupler")
      (fields (field (name "PUBLISHER") "Altium Limited"))
      (libsource (lib "Miscellaneous Devices") (part "Optoisolator1"))
    )
    (comp (ref "U16")
      (value "KP10104CTLD")
      (footprint "KP10104CTLD")
      (description "4-Pin Phototransistor Optocoupler")
      (fields (field (name "PUBLISHER") "Altium Limited"))
      (libsource (lib "Miscellaneous Devices") (part "Optoisolator1"))
    )
    (comp (ref "Y1")
      (value "XTAL")
      (footprint "OSC_5032_2Pin")
      (description "Crystal Oscillator")
      (fields (field (name "PUBLISHER") "Altium Limited"))
      (libsource (lib "Miscellaneous Devices") (part "XTAL"))
    )
  )
  (nets
    (net (code "1") (name "+3.3V") (class "Default")
      (node (ref "C10") (pin "1") (pinfunction "1_1") (pintype "passive"))
      (node (ref "C11") (pin "1") (pinfunction "1_1") (pintype "passive"))
      (node (ref "C13") (pin "1") (pinfunction "1_1") (pintype "passive"))
      (node (ref "C14") (pin "1") (pinfunction "1_1") (pintype "passive"))
      (node (ref "C18") (pin "2") (pinfunction "2_2") (pintype "passive"))
      (node (ref "C19") (pin "2") (pinfunction "2_2") (pintype "passive"))
      (node (ref "C27") (pin "2") (pinfunction "2_2") (pintype "passive"))
      (node (ref "C28") (pin "2") (pinfunction "2_2") (pintype "passive"))
      (node (ref "C37") (pin "1") (pinfunction "1_1") (pintype "passive"))
      (node (ref "C38") (pin "1") (pinfunction "1_1") (pintype "passive"))
      (node (ref "C43") (pin "1") (pinfunction "1_1") (pintype "passive"))
      (node (ref "C44") (pin "1") (pinfunction "1_1") (pintype "passive"))
      (node (ref "P12") (pin "1") (pinfunction "1_1") (pintype "passive"))
      (node (ref "R11") (pin "2") (pinfunction "2_2") (pintype "passive"))
      (node (ref "R15") (pin "2") (pinfunction "2_2") (pintype "passive"))
      (node (ref "R19") (pin "2") (pinfunction "2_2") (pintype "passive"))
      (node (ref "R24") (pin "2") (pinfunction "2_2") (pintype "passive"))
      (node (ref "R25") (pin "2") (pinfunction "2_2") (pintype "passive"))
      (node (ref "R29") (pin "2") (pinfunction "2_2") (pintype "passive"))
      (node (ref "R30") (pin "2") (pinfunction "2_2") (pintype "passive"))
      (node (ref "R34") (pin "2") (pinfunction "2_2") (pintype "passive"))
      (node (ref "R35") (pin "2") (pinfunction "2_2") (pintype "passive"))
      (node (ref "R38") (pin "2") (pinfunction "2_2") (pintype "passive"))
      (node (ref "R39") (pin "2") (pinfunction "2_2") (pintype "passive"))
      (node (ref "R48") (pin "8") (pinfunction "VCC_8") (pintype "passive"))
      (node (ref "R57") (pin "1") (pinfunction "1_1") (pintype "passive"))
      (node (ref "R6") (pin "2") (pinfunction "2_2") (pintype "passive"))
      (node (ref "U10") (pin "13") (pinfunction "VDDA_13") (pintype "power_in"))
      (node (ref "U10") (pin "19") (pinfunction "VDD_4_19") (pintype "power_in"))
      (node (ref "U10") (pin "32") (pinfunction "VDD_1_32") (pintype "power_in"))
      (node (ref "U10") (pin "48") (pinfunction "VDD_2_48") (pintype "power_in"))
      (node (ref "U10") (pin "64") (pinfunction "VDD_3_64") (pintype "power_in"))
      (node (ref "U4") (pin "4") (pinfunction "Vout_4") (pintype "passive"))
      (node (ref "U5") (pin "1") (pinfunction "RST_1") (pintype "passive"))
      (node (ref "U5") (pin "8") (pinfunction "VCC_8") (pintype "passive"))
      (node (ref "U7") (pin "3") (pinfunction "VDD_3") (pintype "passive"))
      (node (ref "U8") (pin "1") (pinfunction "VDDIO_1") (pintype "passive"))
      (node (ref "U8") (pin "14") (pinfunction "VDD_14") (pintype "passive"))
    )
    (net (code "2") (name "+5V") (class "Default")
      (node (ref "C2") (pin "1") (pinfunction "1_1") (pintype "passive"))
      (node (ref "C8") (pin "1") (pinfunction "1_1") (pintype "passive"))
      (node (ref "D12") (pin "2") (pinfunction "K_2") (pintype "passive"))
      (node (ref "D14") (pin "2") (pinfunction "K_2") (pintype "passive"))
      (node (ref "D16") (pin "2") (pinfunction "K_2") (pintype "passive"))
      (node (ref "D6") (pin "2") (pinfunction "K_2") (pintype "passive"))
      (node (ref "D8") (pin "2") (pinfunction "K_2") (pintype "passive"))
      (node (ref "D9") (pin "2") (pinfunction "K_2") (pintype "passive"))
      (node (ref "L1") (pin "2") (pinfunction "2_2") (pintype "passive"))
      (node (ref "LS1") (pin "1") (pinfunction "1_1") (pintype "passive"))
      (node (ref "P13") (pin "1") (pinfunction "1_1") (pintype "passive"))
      (node (ref "P7") (pin "1") (pinfunction "1_1") (pintype "passive"))
      (node (ref "P8") (pin "10") (pinfunction "VDD_10") (pintype "passive"))
      (node (ref "R1") (pin "1") (pinfunction "1_1") (pintype "passive"))
      (node (ref "R10") (pin "1") (pinfunction "1_1") (pintype "passive"))
      (node (ref "R13") (pin "1") (pinfunction "1_1") (pintype "passive"))
      (node (ref "R17") (pin "1") (pinfunction "1_1") (pintype "passive"))
      (node (ref "U1") (pin "1") (pinfunction "A_1") (pintype "passive"))
      (node (ref "U1") (pin "2") (pinfunction "H_2") (pintype "passive"))
      (node (ref "U11") (pin "8") (pinfunction "V+_8") (pintype "power_in"))
      (node (ref "U12") (pin "8") (pinfunction "V+_8") (pintype "power_in"))
      (node (ref "U16") (pin "1") (pinfunction "A_1") (pintype "passive"))
      (node (ref "U2") (pin "6") (pinfunction "VS_6") (pintype "power_in"))
      (node (ref "U3") (pin "4") (pinfunction "FB_4") (pintype "input"))
      (node (ref "U4") (pin "3") (pinfunction "Vin_3") (pintype "passive"))
      (node (ref "U6") (pin "8") (pinfunction "V+_8") (pintype "power_in"))
      (node (ref "U9") (pin "8") (pinfunction "V+_8") (pintype "power_in"))
    )
    (net (code "3") (name "+12V") (class "Default")
      (node (ref "C12") (pin "1") (pinfunction "1_1") (pintype "passive"))
      (node (ref "C4") (pin "1") (pinfunction "1_1") (pintype "passive"))
      (node (ref "C5") (pin "1") (pinfunction "1_1") (pintype "passive"))
      (node (ref "C7") (pin "1") (pinfunction "1_1") (pintype "passive"))
      (node (ref "C9") (pin "1") (pinfunction "1_1") (pintype "passive"))
      (node (ref "CB1") (pin "2") (pinfunction "2_2") (pintype "passive"))
      (node (ref "D1") (pin "2") (pinfunction "K_2") (pintype "passive"))
      (node (ref "D3") (pin "2") (pinfunction "K_2") (pintype "passive"))
      (node (ref "D5") (pin "2") (pinfunction "K_2") (pintype "passive"))
      (node (ref "P2") (pin "1") (pinfunction "1_1") (pintype "passive"))
      (node (ref "P4") (pin "1") (pinfunction "1_1") (pintype "passive"))
      (node (ref "P6") (pin "1") (pinfunction "1_1") (pintype "passive"))
      (node (ref "P9") (pin "1") (pinfunction "1_1") (pintype "passive"))
      (node (ref "R4") (pin "2") (pinfunction "2_2") (pintype "passive"))
      (node (ref "U3") (pin "1") (pinfunction "VIN_1") (pintype "power_in"))
    )
    (net (code "4") (name "/ADH_IN") (class "Default")
      (node (ref "C17") (pin "2") (pinfunction "2_2") (pintype "passive"))
      (node (ref "D6") (pin "1") (pinfunction "A_1") (pintype "passive"))
      (node (ref "D7") (pin "2") (pinfunction "K_2") (pintype "passive"))
      (node (ref "R26") (pin "1") (pinfunction "1_1") (pintype "passive"))
      (node (ref "U10") (pin "17") (pinfunction "PA3_17") (pintype "bidirectional"))
    )
    (net (code "5") (name "/ADH_OUT") (class "Default")
      (node (ref "C15") (pin "2") (pinfunction "2_2") (pintype "passive"))
      (node (ref "P5") (pin "1") (pinfunction "1_1") (pintype "passive"))
      (node (ref "R27") (pin "2") (pinfunction "2_2") (pintype "passive"))
    )
    (net (code "6") (name "/ADL_IN") (class "Default")
      (node (ref "C26") (pin "2") (pinfunction "2_2") (pintype "passive"))
      (node (ref "D11") (pin "2") (pinfunction "K_2") (pintype "passive"))
      (node (ref "D9") (pin "1") (pinfunction "A_1") (pintype "passive"))
      (node (ref "R32") (pin "1") (pinfunction "1_1") (pintype "passive"))
      (node (ref "U10") (pin "21") (pinfunction "PA5_21") (pintype "bidirectional"))
    )
    (net (code "7") (name "/ADL_OUT") (class "Default")
      (node (ref "C24") (pin "2") (pinfunction "2_2") (pintype "passive"))
      (node (ref "P5") (pin "2") (pinfunction "2_2") (pintype "passive"))
      (node (ref "R36") (pin "2") (pinfunction "2_2") (pintype "passive"))
    )
    (net (code "8") (name "/AUDIO") (class "Default")
      (node (ref "C1") (pin "1") (pinfunction "1_1") (pintype "passive"))
      (node (ref "U10") (pin "20") (pinfunction "PA4_20") (pintype "bidirectional"))
    )
    (net (code "9") (name "/Alcohol_C") (class "Default")
      (node (ref "R5") (pin "1") (pinfunction "1_1") (pintype "passive"))
      (node (ref "U1") (pin "6") (pinfunction "B_6") (pintype "passive"))
      (node (ref "U10") (pin "24") (pinfunction "PC4_24") (pintype "bidirectional"))
    )
    (net (code "10") (name "/Bee") (class "Default")
      (node (ref "R14") (pin "2") (pinfunction "2_2") (pintype "passive"))
      (node (ref "U10") (pin "38") (pinfunction "PC7_38") (pintype "bidirectional"))
    )
    (net (code "11") (name "/Debug_Rx") (class "Default")
      (node (ref "P13") (pin "3") (pinfunction "3_3") (pintype "passive"))
      (node (ref "U10") (pin "43") (pinfunction "PA10_43") (pintype "bidirectional"))
    )
    (net (code "12") (name "/Debug_Tx") (class "Default")
      (node (ref "P13") (pin "2") (pinfunction "2_2") (pintype "passive"))
      (node (ref "U10") (pin "42") (pinfunction "PA9_42") (pintype "bidirectional"))
    )
    (net (code "13") (name "/E2_SCL") (class "Default")
      (node (ref "R48") (pin "6") (pinfunction "SCL_6") (pintype "passive"))
      (node (ref "U10") (pin "25") (pinfunction "PC5_25") (pintype "bidirectional"))
    )
    (net (code "14") (name "/E2_SDA") (class "Default")
      (node (ref "R48") (pin "5") (pinfunction "SDA_5") (pintype "passive"))
      (node (ref "U10") (pin "26") (pinfunction "PB0_26") (pintype "bidirectional"))
    )
    (net (code "15") (name "/FHD_IN") (class "Default")
      (node (ref "C31") (pin "2") (pinfunction "2_2") (pintype "passive"))
      (node (ref "D12") (pin "1") (pinfunction "A_1") (pintype "passive"))
      (node (ref "D13") (pin "2") (pinfunction "K_2") (pintype "passive"))
      (node (ref "R40") (pin "1") (pinfunction "1_1") (pintype "passive"))
      (node (ref "U10") (pin "14") (pinfunction "PA0-WKUP_14") (pintype "bidirectional"))
    )
    (net (code "16") (name "/FHD_OUT") (class "Default")
      (node (ref "C19") (pin "1") (pinfunction "1_1") (pintype "passive"))
      (node (ref "C29") (pin "2") (pinfunction "2_2") (pintype "passive"))
      (node (ref "P10") (pin "1") (pinfunction "1_1") (pintype "passive"))
      (node (ref "R35") (pin "1") (pinfunction "1_1") (pintype "passive"))
      (node (ref "R41") (pin "2") (pinfunction "2_2") (pintype "passive"))
    )
    (net (code "17") (name "/FLD_IN") (class "Default")
      (node (ref "C23") (pin "2") (pinfunction "2_2") (pintype "passive"))
      (node (ref "D10") (pin "2") (pinfunction "K_2") (pintype "passive"))
      (node (ref "D8") (pin "1") (pinfunction "A_1") (pintype "passive"))
      (node (ref "R31") (pin "1") (pinfunction "1_1") (pintype "passive"))
      (node (ref "U10") (pin "11") (pinfunction "PC3_11") (pintype "bidirectional"))
    )
    (net (code "18") (name "/FLD_OUT") (class "Default")
      (node (ref "C18") (pin "1") (pinfunction "1_1") (pintype "passive"))
      (node (ref "C21") (pin "2") (pinfunction "2_2") (pintype "passive"))
      (node (ref "P10") (pin "2") (pinfunction "2_2") (pintype "passive"))
      (node (ref "R33") (pin "2") (pinfunction "2_2") (pintype "passive"))
      (node (ref "R34") (pin "1") (pinfunction "1_1") (pintype "passive"))
    )
    (net (code "19") (name "/Fan") (class "Default")
      (node (ref "R15") (pin "1") (pinfunction "1_1") (pintype "passive"))
      (node (ref "R16") (pin "1") (pinfunction "1_1") (pintype "passive"))
      (node (ref "R43") (pin "2") (pinfunction "2_2") (pintype "passive"))
      (node (ref "U10") (pin "28") (pinfunction "PB2_28") (pintype "bidirectional"))
    )
    (net (code "20") (name "/Fire_Tem_D") (class "Default")
      (node (ref "R46") (pin "1") (pinfunction "1_1") (pintype "passive"))
      (node (ref "R47") (pin "2") (pinfunction "2_2") (pintype "passive"))
      (node (ref "U10") (pin "8") (pinfunction "PC0_8") (pintype "bidirectional"))
    )
    (net (code "21") (name "/Fire_Tem_T") (class "Default")
      (node (ref "R55") (pin "1") (pinfunction "1_1") (pintype "passive"))
      (node (ref "R56") (pin "2") (pinfunction "2_2") (pintype "passive"))
      (node (ref "U10") (pin "9") (pinfunction "PC1_9") (pintype "bidirectional"))
    )
    (net (code "22") (name "/Fire_UP") (class "Default")
      (node (ref "R11") (pin "1") (pinfunction "1_1") (pintype "passive"))
      (node (ref "R12") (pin "1") (pinfunction "1_1") (pintype "passive"))
      (node (ref "U10") (pin "10") (pinfunction "PC2_10") (pintype "bidirectional"))
    )
    (net (code "23") (name "/IO1") (class "Default")
      (node (ref "R61") (pin "1") (pinfunction "1_1") (pintype "passive"))
      (node (ref "U10") (pin "58") (pinfunction "PB6_58") (pintype "bidirectional"))
    )
    (net (code "24") (name "/IO2") (class "Default")
      (node (ref "R61") (pin "2") (pinfunction "2_2") (pintype "passive"))
      (node (ref "U10") (pin "59") (pinfunction "PB7_59") (pintype "bidirectional"))
    )
    (net (code "25") (name "/IO3") (class "Default")
      (node (ref "R61") (pin "3") (pinfunction "3_3") (pintype "passive"))
      (node (ref "U10") (pin "61") (pinfunction "PB8_61") (pintype "bidirectional"))
    )
    (net (code "26") (name "/IO4") (class "Default")
      (node (ref "R61") (pin "4") (pinfunction "4_4") (pintype "passive"))
      (node (ref "U10") (pin "62") (pinfunction "PB9_62") (pintype "bidirectional"))
    )
    (net (code "27") (name "/LDHD_IN") (class "Default")
      (node (ref "C42") (pin "2") (pinfunction "2_2") (pintype "passive"))
      (node (ref "D16") (pin "1") (pinfunction "A_1") (pintype "passive"))
      (node (ref "D17") (pin "2") (pinfunction "K_2") (pintype "passive"))
      (node (ref "R58") (pin "1") (pinfunction "1_1") (pintype "passive"))
      (node (ref "U10") (pin "23") (pinfunction "PA7_23") (pintype "bidirectional"))
    )
    (net (code "28") (name "/LDHD_OUT") (class "Default")
      (node (ref "C28") (pin "1") (pinfunction "1_1") (pintype "passive"))
      (node (ref "C40") (pin "2") (pinfunction "2_2") (pintype "passive"))
      (node (ref "P11") (pin "1") (pinfunction "1_1") (pintype "passive"))
      (node (ref "R39") (pin "1") (pinfunction "1_1") (pintype "passive"))
      (node (ref "R59") (pin "2") (pinfunction "2_2") (pintype "passive"))
    )
    (net (code "29") (name "/LDLD_IN") (class "Default")
      (node (ref "C36") (pin "2") (pinfunction "2_2") (pintype "passive"))
      (node (ref "D14") (pin "1") (pinfunction "A_1") (pintype "passive"))
      (node (ref "D15") (pin "2") (pinfunction "K_2") (pintype "passive"))
      (node (ref "R49") (pin "1") (pinfunction "1_1") (pintype "passive"))
      (node (ref "U10") (pin "22") (pinfunction "PA6_22") (pintype "bidirectional"))
    )
    (net (code "30") (name "/LDLD_OUT") (class "Default")
      (node (ref "C27") (pin "1") (pinfunction "1_1") (pintype "passive"))
      (node (ref "C34") (pin "2") (pinfunction "2_2") (pintype "passive"))
      (node (ref "P11") (pin "2") (pinfunction "2_2") (pintype "passive"))
      (node (ref "R38") (pin "1") (pinfunction "1_1") (pintype "passive"))
      (node (ref "R50") (pin "2") (pinfunction "2_2") (pintype "passive"))
    )
    (net (code "31") (name "/MMA_SCL") (class "Default")
      (node (ref "R29") (pin "1") (pinfunction "1_1") (pintype "passive"))
      (node (ref "U10") (pin "57") (pinfunction "PB5_57") (pintype "bidirectional"))
      (node (ref "U8") (pin "4") (pinfunction "SCL_4") (pintype "passive"))
    )
    (net (code "32") (name "/MMA_SDA") (class "Default")
      (node (ref "R30") (pin "1") (pinfunction "1_1") (pintype "passive"))
      (node (ref "U10") (pin "56") (pinfunction "PB4_56") (pintype "bidirectional"))
      (node (ref "U8") (pin "6") (pinfunction "SDA_6") (pintype "passive"))
    )
    (net (code "33") (name "/Pump1") (class "Default")
      (node (ref "R19") (pin "1") (pinfunction "1_1") (pintype "passive"))
      (node (ref "R22") (pin "1") (pinfunction "1_1") (pintype "passive"))
      (node (ref "U10") (pin "15") (pinfunction "PA1_15") (pintype "bidirectional"))
    )
    (net (code "34") (name "/Pump2") (class "Default")
      (node (ref "R6") (pin "1") (pinfunction "1_1") (pintype "passive"))
      (node (ref "R7") (pin "1") (pinfunction "1_1") (pintype "passive"))
      (node (ref "U10") (pin "16") (pinfunction "PA2_16") (pintype "bidirectional"))
    )
    (net (code "35") (name "/SR_D0") (class "Default")
      (node (ref "R20") (pin "2") (pinfunction "2_2") (pintype "passive"))
      (node (ref "U10") (pin "35") (pinfunction "PB14_35") (pintype "bidirectional"))
    )
    (net (code "36") (name "/SR_D1") (class "Default")
      (node (ref "R21") (pin "2") (pinfunction "2_2") (pintype "passive"))
      (node (ref "U10") (pin "36") (pinfunction "PB15_36") (pintype "bidirectional"))
    )
    (net (code "37") (name "/SR_D2") (class "Default")
      (node (ref "R23") (pin "2") (pinfunction "2_2") (pintype "passive"))
      (node (ref "U10") (pin "37") (pinfunction "PC6_37") (pintype "bidirectional"))
    )
    (net (code "38") (name "/SR_LED") (class "Default")
      (node (ref "R62") (pin "2") (pinfunction "2_2") (pintype "passive"))
      (node (ref "U10") (pin "33") (pinfunction "PB12_33") (pintype "bidirectional"))
    )
    (net (code "39") (name "/SR_SW") (class "Default")
      (node (ref "R18") (pin "2") (pinfunction "2_2") (pintype "passive"))
      (node (ref "U10") (pin "34") (pinfunction "PB13_34") (pintype "bidirectional"))
    )
    (net (code "40") (name "/SW1") (class "Default")
      (node (ref "S1") (pin "1") (pinfunction "A1_1") (pintype "passive"))
      (node (ref "U10") (pin "51") (pinfunction "PC10_51") (pintype "bidirectional"))
    )
    (net (code "41") (name "/SW2") (class "Default")
      (node (ref "S1") (pin "2") (pinfunction "A2_2") (pintype "passive"))
      (node (ref "U10") (pin "52") (pinfunction "PC11_52") (pintype "bidirectional"))
    )
    (net (code "42") (name "/SW3") (class "Default")
      (node (ref "S1") (pin "3") (pinfunction "A3_3") (pintype "passive"))
      (node (ref "U10") (pin "53") (pinfunction "PC12_53") (pintype "bidirectional"))
    )
    (net (code "43") (name "/SW4") (class "Default")
      (node (ref "S1") (pin "4") (pinfunction "A4_4") (pintype "passive"))
      (node (ref "U10") (pin "54") (pinfunction "PD2_54") (pintype "bidirectional"))
    )
    (net (code "44") (name "/SW5") (class "Default")
      (node (ref "S1") (pin "5") (pinfunction "A5_5") (pintype "passive"))
      (node (ref "U10") (pin "45") (pinfunction "PA12_45") (pintype "bidirectional"))
    )
    (net (code "45") (name "/SW6") (class "Default")
      (node (ref "S1") (pin "6") (pinfunction "A6_6") (pintype "passive"))
      (node (ref "U10") (pin "44") (pinfunction "PA11_44") (pintype "bidirectional"))
    )
    (net (code "46") (name "/SW7") (class "Default")
      (node (ref "S1") (pin "7") (pinfunction "A7_7") (pintype "passive"))
      (node (ref "U10") (pin "40") (pinfunction "PC9_40") (pintype "bidirectional"))
    )
    (net (code "47") (name "/SW8") (class "Default")
      (node (ref "S1") (pin "8") (pinfunction "A8_8") (pintype "passive"))
      (node (ref "U10") (pin "39") (pinfunction "PC8_39") (pintype "bidirectional"))
    )
    (net (code "48") (name "/SWCLK") (class "Default")
      (node (ref "P12") (pin "3") (pinfunction "3_3") (pintype "passive"))
      (node (ref "U10") (pin "49") (pinfunction "PA14_49") (pintype "bidirectional"))
    )
    (net (code "49") (name "/SWDIO") (class "Default")
      (node (ref "P12") (pin "2") (pinfunction "2_2") (pintype "passive"))
      (node (ref "U10") (pin "46") (pinfunction "PA13_46") (pintype "bidirectional"))
    )
    (net (code "50") (name "/Tem") (class "Default")
      (node (ref "R25") (pin "1") (pinfunction "1_1") (pintype "passive"))
      (node (ref "U10") (pin "27") (pinfunction "PB1_27") (pintype "bidirectional"))
      (node (ref "U7") (pin "2") (pinfunction "DQ_2") (pintype "passive"))
    )
    (net (code "51") (name "/WIFI_RX") (class "Default")
      (node (ref "U10") (pin "29") (pinfunction "PB10_29") (pintype "bidirectional"))
      (node (ref "U5") (pin "15") (pinfunction "RXD0_15") (pintype "passive"))
    )
    (net (code "52") (name "/WIFI_TX") (class "Default")
      (node (ref "U10") (pin "30") (pinfunction "PB11_30") (pintype "bidirectional"))
      (node (ref "U5") (pin "16") (pinfunction "TXD0_16") (pintype "passive"))
    )
    (net (code "53") (name "Net-(C1-Pad2)") (class "Default")
      (node (ref "C1") (pin "2") (pinfunction "2_2") (pintype "passive"))
      (node (ref "R2") (pin "2") (pinfunction "2_2") (pintype "passive"))
    )
    (net (code "54") (name "Net-(C3-Pad2)") (class "Default")
      (node (ref "C3") (pin "2") (pinfunction "2_2") (pintype "passive"))
      (node (ref "P3") (pin "1") (pinfunction "1_1") (pintype "passive"))
    )
    (net (code "55") (name "Net-(C6-Pad1)") (class "Default")
      (node (ref "C6") (pin "1") (pinfunction "1_1") (pintype "passive"))
      (node (ref "R9") (pin "2") (pinfunction "2_2") (pintype "passive"))
    )
    (net (code "56") (name "Net-(CB1-Pad1)") (class "Default")
      (node (ref "CB1") (pin "1") (pinfunction "1_1") (pintype "passive"))
      (node (ref "P1") (pin "1") (pinfunction "1_1") (pintype "passive"))
    )
    (net (code "57") (name "Net-(D1-A)") (class "Default")
      (node (ref "C4") (pin "2") (pinfunction "2_2") (pintype "passive"))
      (node (ref "C5") (pin "2") (pinfunction "2_2") (pintype "passive"))
      (node (ref "D1") (pin "1") (pinfunction "A_1") (pintype "passive"))
      (node (ref "P2") (pin "2") (pinfunction "2_2") (pintype "passive"))
      (node (ref "Q1") (pin "2") (pinfunction "D_2") (pintype "passive"))
    )
    (net (code "58") (name "Net-(D2-A)") (class "Default")
      (node (ref "D2") (pin "1") (pinfunction "A_1") (pintype "passive"))
      (node (ref "R4") (pin "1") (pinfunction "1_1") (pintype "passive"))
    )
    (net (code "59") (name "Net-(D3-A)") (class "Default")
      (node (ref "C9") (pin "2") (pinfunction "2_2") (pintype "passive"))
      (node (ref "D3") (pin "1") (pinfunction "A_1") (pintype "passive"))
      (node (ref "P6") (pin "2") (pinfunction "2_2") (pintype "passive"))
      (node (ref "Q6") (pin "2") (pinfunction "D_2") (pintype "passive"))
    )
    (net (code "60") (name "Net-(D4-K)") (class "Default")
      (node (ref "D4") (pin "2") (pinfunction "K_2") (pintype "passive"))
      (node (ref "L1") (pin "1") (pinfunction "1_1") (pintype "passive"))
      (node (ref "U3") (pin "2") (pinfunction "OUT_2") (pintype "power_in"))
    )
    (net (code "61") (name "Net-(D5-A)") (class "Default")
      (node (ref "C12") (pin "2") (pinfunction "2_2") (pintype "passive"))
      (node (ref "D5") (pin "1") (pinfunction "A_1") (pintype "passive"))
      (node (ref "P9") (pin "2") (pinfunction "2_2") (pintype "passive"))
      (node (ref "Q8") (pin "2") (pinfunction "D_2") (pintype "passive"))
    )
    (net (code "62") (name "Net-(P7-Pad2)") (class "Default")
      (node (ref "P7") (pin "2") (pinfunction "2_2") (pintype "passive"))
      (node (ref "R60") (pin "8") (pinfunction "8_8") (pintype "passive"))
    )
    (net (code "63") (name "Net-(P7-Pad3)") (class "Default")
      (node (ref "P7") (pin "3") (pinfunction "3_3") (pintype "passive"))
      (node (ref "R60") (pin "7") (pinfunction "7_7") (pintype "passive"))
    )
    (net (code "64") (name "Net-(P7-Pad4)") (class "Default")
      (node (ref "P7") (pin "4") (pinfunction "4_4") (pintype "passive"))
      (node (ref "R60") (pin "6") (pinfunction "6_6") (pintype "passive"))
    )
    (net (code "65") (name "Net-(P7-Pad5)") (class "Default")
      (node (ref "P7") (pin "5") (pinfunction "5_5") (pintype "passive"))
      (node (ref "R60") (pin "5") (pinfunction "5_5") (pintype "passive"))
    )
    (net (code "66") (name "Net-(P8-D0)") (class "Default")
      (node (ref "P8") (pin "6") (pinfunction "D0_6") (pintype "passive"))
      (node (ref "R20") (pin "1") (pinfunction "1_1") (pintype "passive"))
    )
    (net (code "67") (name "Net-(P8-D1)") (class "Default")
      (node (ref "P8") (pin "7") (pinfunction "D1_7") (pintype "passive"))
      (node (ref "R21") (pin "1") (pinfunction "1_1") (pintype "passive"))
    )
    (net (code "68") (name "Net-(P8-D2)") (class "Default")
      (node (ref "P8") (pin "8") (pinfunction "D2_8") (pintype "passive"))
      (node (ref "R23") (pin "1") (pinfunction "1_1") (pintype "passive"))
    )
    (net (code "69") (name "Net-(P8-LED)") (class "Default")
      (node (ref "P8") (pin "3") (pinfunction "LED_3") (pintype "passive"))
      (node (ref "R62") (pin "1") (pinfunction "1_1") (pintype "passive"))
    )
    (net (code "70") (name "Net-(P8-SW)") (class "Default")
      (node (ref "P8") (pin "4") (pinfunction "SW_4") (pintype "passive"))
      (node (ref "R18") (pin "1") (pinfunction "1_1") (pintype "passive"))
    )
    (net (code "71") (name "Net-(P14-Pad1)") (class "Default")
      (node (ref "P14") (pin "1") (pinfunction "1_1") (pintype "passive"))
      (node (ref "R44") (pin "1") (pinfunction "1_1") (pintype "passive"))
    )
    (net (code "72") (name "Net-(P15-Pad1)") (class "Default")
      (node (ref "P15") (pin "1") (pinfunction "1_1") (pintype "passive"))
      (node (ref "R52") (pin "1") (pinfunction "1_1") (pintype "passive"))
    )
    (net (code "73") (name "Net-(Q1-G)") (class "Default")
      (node (ref "Q1") (pin "1") (pinfunction "G_1") (pintype "passive"))
      (node (ref "Q2") (pin "3") (pinfunction "C_3") (pintype "passive"))
      (node (ref "R1") (pin "2") (pinfunction "2_2") (pintype "passive"))
    )
    (net (code "74") (name "Net-(Q2-B)") (class "Default")
      (node (ref "Q2") (pin "1") (pinfunction "B_1") (pintype "passive"))
      (node (ref "R7") (pin "2") (pinfunction "2_2") (pintype "passive"))
    )
    (net (code "75") (name "Net-(Q3-D)") (class "Default")
      (node (ref "P4") (pin "2") (pinfunction "2_2") (pintype "passive"))
      (node (ref "Q3") (pin "2") (pinfunction "D_2") (pintype "passive"))
    )
    (net (code "76") (name "Net-(Q3-G)") (class "Default")
      (node (ref "Q3") (pin "1") (pinfunction "G_1") (pintype "passive"))
      (node (ref "Q4") (pin "3") (pinfunction "C_3") (pintype "passive"))
      (node (ref "R10") (pin "2") (pinfunction "2_2") (pintype "passive"))
    )
    (net (code "77") (name "Net-(Q4-B)") (class "Default")
      (node (ref "Q4") (pin "1") (pinfunction "B_1") (pintype "passive"))
      (node (ref "R12") (pin "2") (pinfunction "2_2") (pintype "passive"))
    )
    (net (code "78") (name "Net-(Q5-B)") (class "Default")
      (node (ref "Q5") (pin "1") (pinfunction "B_1") (pintype "passive"))
      (node (ref "R14") (pin "1") (pinfunction "1_1") (pintype "passive"))
    )
    (net (code "79") (name "Net-(Q5-C)") (class "Default")
      (node (ref "LS1") (pin "2") (pinfunction "2_2") (pintype "passive"))
      (node (ref "Q5") (pin "3") (pinfunction "C_3") (pintype "passive"))
    )
    (net (code "80") (name "Net-(Q6-G)") (class "Default")
      (node (ref "Q6") (pin "1") (pinfunction "G_1") (pintype "passive"))
      (node (ref "Q7") (pin "3") (pinfunction "C_3") (pintype "passive"))
      (node (ref "R13") (pin "2") (pinfunction "2_2") (pintype "passive"))
    )
    (net (code "81") (name "Net-(Q7-B)") (class "Default")
      (node (ref "Q7") (pin "1") (pinfunction "B_1") (pintype "passive"))
      (node (ref "R16") (pin "2") (pinfunction "2_2") (pintype "passive"))
    )
    (net (code "82") (name "Net-(Q8-G)") (class "Default")
      (node (ref "Q8") (pin "1") (pinfunction "G_1") (pintype "passive"))
      (node (ref "Q9") (pin "3") (pinfunction "C_3") (pintype "passive"))
      (node (ref "R17") (pin "2") (pinfunction "2_2") (pintype "passive"))
    )
    (net (code "83") (name "Net-(Q9-B)") (class "Default")
      (node (ref "Q9") (pin "1") (pinfunction "B_1") (pintype "passive"))
      (node (ref "R22") (pin "2") (pinfunction "2_2") (pintype "passive"))
    )
    (net (code "84") (name "Net-(U2-IN+)") (class "Default")
      (node (ref "R2") (pin "1") (pinfunction "1_1") (pintype "passive"))
      (node (ref "R8") (pin "2") (pinfunction "2_2") (pintype "passive"))
      (node (ref "U2") (pin "3") (pinfunction "IN+_3") (pintype "input"))
    )
    (net (code "85") (name "Net-(U2-VOUT)") (class "Default")
      (node (ref "C3") (pin "1") (pinfunction "1_1") (pintype "passive"))
      (node (ref "C6") (pin "2") (pinfunction "2_2") (pintype "passive"))
      (node (ref "U2") (pin "5") (pinfunction "VOUT_5") (pintype "output"))
    )
    (net (code "86") (name "Net-(U5-CH_PD)") (class "Default")
      (node (ref "R24") (pin "1") (pinfunction "1_1") (pintype "passive"))
      (node (ref "U5") (pin "3") (pinfunction "CH_PD_3") (pintype "passive"))
    )
    (net (code "87") (name "Net-(U5-GPIO15)") (class "Default")
      (node (ref "R28") (pin "1") (pinfunction "1_1") (pintype "passive"))
      (node (ref "U5") (pin "10") (pinfunction "GPIO15_10") (pintype "passive"))
    )
    (net (code "88") (name "Net-(U6A-INA+)") (class "Default")
      (node (ref "C16") (pin "2") (pinfunction "2_2") (pintype "passive"))
      (node (ref "R27") (pin "1") (pinfunction "1_1") (pintype "passive"))
      (node (ref "U6") (pin "3") (pinfunction "INA+_3") (pintype "input"))
    )
    (net (code "89") (name "Net-(U6A-INA-)") (class "Default")
      (node (ref "R26") (pin "2") (pinfunction "2_2") (pintype "passive"))
      (node (ref "U6") (pin "1") (pinfunction "OUTA_1") (pintype "output"))
      (node (ref "U6") (pin "2") (pinfunction "INA-_2") (pintype "input"))
    )
    (net (code "90") (name "Net-(U6B-INB+)") (class "Default")
      (node (ref "C25") (pin "2") (pinfunction "2_2") (pintype "passive"))
      (node (ref "R36") (pin "1") (pinfunction "1_1") (pintype "passive"))
      (node (ref "U6") (pin "5") (pinfunction "INB+_5") (pintype "input"))
    )
    (net (code "91") (name "Net-(U6B-INB-)") (class "Default")
      (node (ref "R32") (pin "2") (pinfunction "2_2") (pintype "passive"))
      (node (ref "U6") (pin "6") (pinfunction "INB-_6") (pintype "input"))
      (node (ref "U6") (pin "7") (pinfunction "OUTB_7") (pintype "output"))
    )
    (net (code "92") (name "Net-(U8-BYP)") (class "Default")
      (node (ref "C20") (pin "2") (pinfunction "2_2") (pintype "passive"))
      (node (ref "U8") (pin "2") (pinfunction "BYP_2") (pintype "passive"))
    )
    (net (code "93") (name "Net-(U8-SA0)") (class "Default")
      (node (ref "R37") (pin "2") (pinfunction "2_2") (pintype "passive"))
      (node (ref "U8") (pin "7") (pinfunction "SA0_7") (pintype "passive"))
    )
    (net (code "94") (name "Net-(U9A-INA+)") (class "Default")
      (node (ref "C22") (pin "2") (pinfunction "2_2") (pintype "passive"))
      (node (ref "R33") (pin "1") (pinfunction "1_1") (pintype "passive"))
      (node (ref "U9") (pin "3") (pinfunction "INA+_3") (pintype "input"))
    )
    (net (code "95") (name "Net-(U9A-INA-)") (class "Default")
      (node (ref "R31") (pin "2") (pinfunction "2_2") (pintype "passive"))
      (node (ref "U9") (pin "1") (pinfunction "OUTA_1") (pintype "output"))
      (node (ref "U9") (pin "2") (pinfunction "INA-_2") (pintype "input"))
    )
    (net (code "96") (name "Net-(U9B-INB+)") (class "Default")
      (node (ref "C30") (pin "2") (pinfunction "2_2") (pintype "passive"))
      (node (ref "R41") (pin "1") (pinfunction "1_1") (pintype "passive"))
      (node (ref "U9") (pin "5") (pinfunction "INB+_5") (pintype "input"))
    )
    (net (code "97") (name "Net-(U9B-INB-)") (class "Default")
      (node (ref "R40") (pin "2") (pinfunction "2_2") (pintype "passive"))
      (node (ref "U9") (pin "6") (pinfunction "INB-_6") (pintype "input"))
      (node (ref "U9") (pin "7") (pinfunction "OUTB_7") (pintype "output"))
    )
    (net (code "98") (name "Net-(U10A-BOOT0)") (class "Default")
      (node (ref "R54") (pin "2") (pinfunction "2_2") (pintype "passive"))
      (node (ref "U10") (pin "60") (pinfunction "BOOT0_60") (pintype "input"))
    )
    (net (code "99") (name "Net-(U10A-NRST)") (class "Default")
      (node (ref "C39") (pin "2") (pinfunction "2_2") (pintype "passive"))
      (node (ref "R57") (pin "2") (pinfunction "2_2") (pintype "passive"))
      (node (ref "S2") (pin "2") (pinfunction "2_2") (pintype "passive"))
      (node (ref "U10") (pin "7") (pinfunction "NRST_7") (pintype "bidirectional"))
    )
    (net (code "100") (name "Net-(U10A-PD0-OSC_IN)") (class "Default")
      (node (ref "C32") (pin "1") (pinfunction "1_1") (pintype "passive"))
      (node (ref "U10") (pin "5") (pinfunction "PD0-OSC_IN_5") (pintype "bidirectional"))
      (node (ref "Y1") (pin "2") (pinfunction "OSC2_2") (pintype "passive"))
    )
    (net (code "101") (name "Net-(U10A-PD1)") (class "Default")
      (node (ref "C33") (pin "1") (pinfunction "1_1") (pintype "passive"))
      (node (ref "U10") (pin "6") (pinfunction "PD1_6") (pintype "bidirectional"))
      (node (ref "Y1") (pin "1") (pinfunction "OSC1_1") (pintype "passive"))
    )
    (net (code "102") (name "Net-(U11A-INA+)") (class "Default")
      (node (ref "R45") (pin "2") (pinfunction "2_2") (pintype "passive"))
      (node (ref "U11") (pin "3") (pinfunction "INA+_3") (pintype "input"))
    )
    (net (code "103") (name "Net-(U11A-INA-)") (class "Default")
      (node (ref "R42") (pin "1") (pinfunction "1_1") (pintype "passive"))
      (node (ref "R44") (pin "2") (pinfunction "2_2") (pintype "passive"))
      (node (ref "U11") (pin "2") (pinfunction "INA-_2") (pintype "input"))
    )
    (net (code "104") (name "Net-(U11A-OUTA)") (class "Default")
      (node (ref "R42") (pin "2") (pinfunction "2_2") (pintype "passive"))
      (node (ref "R46") (pin "2") (pinfunction "2_2") (pintype "passive"))
      (node (ref "U11") (pin "1") (pinfunction "OUTA_1") (pintype "output"))
    )
    (net (code "105") (name "Net-(U11B-INB+)") (class "Default")
      (node (ref "R53") (pin "2") (pinfunction "2_2") (pintype "passive"))
      (node (ref "U11") (pin "5") (pinfunction "INB+_5") (pintype "input"))
    )
    (net (code "106") (name "Net-(U11B-INB-)") (class "Default")
      (node (ref "R51") (pin "1") (pinfunction "1_1") (pintype "passive"))
      (node (ref "R52") (pin "2") (pinfunction "2_2") (pintype "passive"))
      (node (ref "U11") (pin "6") (pinfunction "INB-_6") (pintype "input"))
    )
    (net (code "107") (name "Net-(U11B-OUTB)") (class "Default")
      (node (ref "R51") (pin "2") (pinfunction "2_2") (pintype "passive"))
      (node (ref "R55") (pin "2") (pinfunction "2_2") (pintype "passive"))
      (node (ref "U11") (pin "7") (pinfunction "OUTB_7") (pintype "output"))
    )
    (net (code "108") (name "Net-(U12A-INA+)") (class "Default")
      (node (ref "C35") (pin "2") (pinfunction "2_2") (pintype "passive"))
      (node (ref "R50") (pin "1") (pinfunction "1_1") (pintype "passive"))
      (node (ref "U12") (pin "3") (pinfunction "INA+_3") (pintype "input"))
    )
    (net (code "109") (name "Net-(U12A-INA-)") (class "Default")
      (node (ref "R49") (pin "2") (pinfunction "2_2") (pintype "passive"))
      (node (ref "U12") (pin "1") (pinfunction "OUTA_1") (pintype "output"))
      (node (ref "U12") (pin "2") (pinfunction "INA-_2") (pintype "input"))
    )
    (net (code "110") (name "Net-(U12B-INB+)") (class "Default")
      (node (ref "C41") (pin "2") (pinfunction "2_2") (pintype "passive"))
      (node (ref "R59") (pin "1") (pinfunction "1_1") (pintype "passive"))
      (node (ref "U12") (pin "5") (pinfunction "INB+_5") (pintype "input"))
    )
    (net (code "111") (name "Net-(U12B-INB-)") (class "Default")
      (node (ref "R58") (pin "2") (pinfunction "2_2") (pintype "passive"))
      (node (ref "U12") (pin "6") (pinfunction "INB-_6") (pintype "input"))
      (node (ref "U12") (pin "7") (pinfunction "OUTB_7") (pintype "output"))
    )
    (net (code "112") (name "Net-(U13-A)") (class "Default")
      (node (ref "R61") (pin "8") (pinfunction "8_8") (pintype "passive"))
      (node (ref "U13") (pin "1") (pinfunction "A_1") (pintype "passive"))
    )
    (net (code "113") (name "Net-(U13-C)") (class "Default")
      (node (ref "R60") (pin "1") (pinfunction "1_1") (pintype "passive"))
      (node (ref "U13") (pin "4") (pinfunction "C_4") (pintype "passive"))
    )
    (net (code "114") (name "Net-(U14-A)") (class "Default")
      (node (ref "R61") (pin "7") (pinfunction "7_7") (pintype "passive"))
      (node (ref "U14") (pin "1") (pinfunction "A_1") (pintype "passive"))
    )
    (net (code "115") (name "Net-(U14-C)") (class "Default")
      (node (ref "R60") (pin "2") (pinfunction "2_2") (pintype "passive"))
      (node (ref "U14") (pin "4") (pinfunction "C_4") (pintype "passive"))
    )
    (net (code "116") (name "Net-(U15-A)") (class "Default")
      (node (ref "R61") (pin "6") (pinfunction "6_6") (pintype "passive"))
      (node (ref "U15") (pin "1") (pinfunction "A_1") (pintype "passive"))
    )
    (net (code "117") (name "Net-(U15-C)") (class "Default")
      (node (ref "R60") (pin "3") (pinfunction "3_3") (pintype "passive"))
      (node (ref "U15") (pin "4") (pinfunction "C_4") (pintype "passive"))
    )
    (net (code "118") (name "Net-(U16-C)") (class "Default")
      (node (ref "R61") (pin "5") (pinfunction "5_5") (pintype "passive"))
      (node (ref "U16") (pin "4") (pinfunction "C_4") (pintype "passive"))
    )
    (net (code "119") (name "Net-(U16-K)") (class "Default")
      (node (ref "R60") (pin "4") (pinfunction "4_4") (pintype "passive"))
      (node (ref "U16") (pin "2") (pinfunction "K_2") (pintype "passive"))
    )
    (net (code "120") (name "PGND") (class "Default")
      (node (ref "C15") (pin "1") (pinfunction "1_1") (pintype "passive"))
      (node (ref "C16") (pin "1") (pinfunction "1_1") (pintype "passive"))
      (node (ref "C17") (pin "1") (pinfunction "1_1") (pintype "passive"))
      (node (ref "C2") (pin "2") (pinfunction "2_2") (pintype "passive"))
      (node (ref "C21") (pin "1") (pinfunction "1_1") (pintype "passive"))
      (node (ref "C22") (pin "1") (pinfunction "1_1") (pintype "passive"))
      (node (ref "C23") (pin "1") (pinfunction "1_1") (pintype "passive"))
      (node (ref "C24") (pin "1") (pinfunction "1_1") (pintype "passive"))
      (node (ref "C25") (pin "1") (pinfunction "1_1") (pintype "passive"))
      (node (ref "C26") (pin "1") (pinfunction "1_1") (pintype "passive"))
      (node (ref "C29") (pin "1") (pinfunction "1_1") (pintype "passive"))
      (node (ref "C30") (pin "1") (pinfunction "1_1") (pintype "passive"))
      (node (ref "C31") (pin "1") (pinfunction "1_1") (pintype "passive"))
      (node (ref "C34") (pin "1") (pinfunction "1_1") (pintype "passive"))
      (node (ref "C35") (pin "1") (pinfunction "1_1") (pintype "passive"))
      (node (ref "C36") (pin "1") (pinfunction "1_1") (pintype "passive"))
      (node (ref "C40") (pin "1") (pinfunction "1_1") (pintype "passive"))
      (node (ref "C41") (pin "1") (pinfunction "1_1") (pintype "passive"))
      (node (ref "C42") (pin "1") (pinfunction "1_1") (pintype "passive"))
      (node (ref "C7") (pin "2") (pinfunction "2_2") (pintype "passive"))
      (node (ref "C8") (pin "2") (pinfunction "2_2") (pintype "passive"))
      (node (ref "D10") (pin "1") (pinfunction "A_1") (pintype "passive"))
      (node (ref "D11") (pin "1") (pinfunction "A_1") (pintype "passive"))
      (node (ref "D13") (pin "1") (pinfunction "A_1") (pintype "passive"))
      (node (ref "D15") (pin "1") (pinfunction "A_1") (pintype "passive"))
      (node (ref "D17") (pin "1") (pinfunction "A_1") (pintype "passive"))
      (node (ref "D2") (pin "2") (pinfunction "K_2") (pintype "passive"))
      (node (ref "D4") (pin "1") (pinfunction "A_1") (pintype "passive"))
      (node (ref "D7") (pin "1") (pinfunction "A_1") (pintype "passive"))
      (node (ref "P1") (pin "2") (pinfunction "2_2") (pintype "passive"))
      (node (ref "P10") (pin "3") (pinfunction "3_3") (pintype "passive"))
      (node (ref "P11") (pin "3") (pinfunction "3_3") (pintype "passive"))
      (node (ref "P14") (pin "2") (pinfunction "2_2") (pintype "passive"))
      (node (ref "P15") (pin "2") (pinfunction "2_2") (pintype "passive"))
      (node (ref "P3") (pin "2") (pinfunction "2_2") (pintype "passive"))
      (node (ref "P5") (pin "3") (pinfunction "3_3") (pintype "passive"))
      (node (ref "P7") (pin "7") (pinfunction "7_7") (pintype "passive"))
      (node (ref "P8") (pin "11") (pinfunction "GND_11") (pintype "passive"))
      (node (ref "P8") (pin "2") (pinfunction "GND_2") (pintype "passive"))
      (node (ref "Q1") (pin "3") (pinfunction "S_3") (pintype "passive"))
      (node (ref "Q3") (pin "3") (pinfunction "S_3") (pintype "passive"))
      (node (ref "Q5") (pin "2") (pinfunction "E_2") (pintype "passive"))
      (node (ref "Q6") (pin "3") (pinfunction "S_3") (pintype "passive"))
      (node (ref "Q8") (pin "3") (pinfunction "S_3") (pintype "passive"))
      (node (ref "R3") (pin "1") (pinfunction "1_1") (pintype "passive"))
      (node (ref "R45") (pin "1") (pinfunction "1_1") (pintype "passive"))
      (node (ref "R47") (pin "1") (pinfunction "1_1") (pintype "passive"))
      (node (ref "R5") (pin "2") (pinfunction "2_2") (pintype "passive"))
      (node (ref "R53") (pin "1") (pinfunction "1_1") (pintype "passive"))
      (node (ref "R56") (pin "1") (pinfunction "1_1") (pintype "passive"))
      (node (ref "R9") (pin "1") (pinfunction "1_1") (pintype "passive"))
      (node (ref "U1") (pin "5") (pinfunction "H_5") (pintype "passive"))
      (node (ref "U11") (pin "4") (pinfunction "GND_4") (pintype "power_in"))
      (node (ref "U12") (pin "4") (pinfunction "GND_4") (pintype "power_in"))
      (node (ref "U13") (pin "3") (pinfunction "E_3") (pintype "passive"))
      (node (ref "U14") (pin "3") (pinfunction "E_3") (pintype "passive"))
      (node (ref "U15") (pin "3") (pinfunction "E_3") (pintype "passive"))
      (node (ref "U2") (pin "4") (pinfunction "GND_4") (pintype "power_in"))
      (node (ref "U3") (pin "3") (pinfunction "GND_3") (pintype "power_in"))
      (node (ref "U3") (pin "5") (pinfunction "~{ON}/OFF_5") (pintype "input"))
      (node (ref "U6") (pin "4") (pinfunction "GND_4") (pintype "power_in"))
      (node (ref "U9") (pin "4") (pinfunction "GND_4") (pintype "power_in"))
    )
    (net (code "121") (name "SGND") (class "Default")
      (node (ref "C10") (pin "2") (pinfunction "2_2") (pintype "passive"))
      (node (ref "C11") (pin "2") (pinfunction "2_2") (pintype "passive"))
      (node (ref "C13") (pin "2") (pinfunction "2_2") (pintype "passive"))
      (node (ref "C14") (pin "2") (pinfunction "2_2") (pintype "passive"))
      (node (ref "C20") (pin "1") (pinfunction "1_1") (pintype "passive"))
      (node (ref "C32") (pin "2") (pinfunction "2_2") (pintype "passive"))
      (node (ref "C33") (pin "2") (pinfunction "2_2") (pintype "passive"))
      (node (ref "C37") (pin "2") (pinfunction "2_2") (pintype "passive"))
      (node (ref "C38") (pin "2") (pinfunction "2_2") (pintype "passive"))
      (node (ref "C39") (pin "1") (pinfunction "1_1") (pintype "passive"))
      (node (ref "C43") (pin "2") (pinfunction "2_2") (pintype "passive"))
      (node (ref "C44") (pin "2") (pinfunction "2_2") (pintype "passive"))
      (node (ref "P12") (pin "4") (pinfunction "4_4") (pintype "passive"))
      (node (ref "P13") (pin "4") (pinfunction "4_4") (pintype "passive"))
      (node (ref "Q2") (pin "2") (pinfunction "E_2") (pintype "passive"))
      (node (ref "Q4") (pin "2") (pinfunction "E_2") (pintype "passive"))
      (node (ref "Q7") (pin "2") (pinfunction "E_2") (pintype "passive"))
      (node (ref "Q9") (pin "2") (pinfunction "E_2") (pintype "passive"))
      (node (ref "R28") (pin "2") (pinfunction "2_2") (pintype "passive"))
      (node (ref "R3") (pin "2") (pinfunction "2_2") (pintype "passive"))
      (node (ref "R37") (pin "1") (pinfunction "1_1") (pintype "passive"))
      (node (ref "R43") (pin "1") (pinfunction "1_1") (pintype "passive"))
      (node (ref "R48") (pin "1") (pinfunction "A0_1") (pintype "passive"))
      (node (ref "R48") (pin "2") (pinfunction "A1_2") (pintype "passive"))
      (node (ref "R48") (pin "3") (pinfunction "A2_3") (pintype "passive"))
      (node (ref "R48") (pin "4") (pinfunction "GND_4") (pintype "passive"))
      (node (ref "R48") (pin "7") (pinfunction "WP_7") (pintype "passive"))
      (node (ref "R54") (pin "1") (pinfunction "1_1") (pintype "passive"))
      (node (ref "R8") (pin "1") (pinfunction "1_1") (pintype "passive"))
      (node (ref "S1") (pin "10") (pinfunction "B7_10") (pintype "passive"))
      (node (ref "S1") (pin "11") (pinfunction "B6_11") (pintype "passive"))
      (node (ref "S1") (pin "12") (pinfunction "B5_12") (pintype "passive"))
      (node (ref "S1") (pin "13") (pinfunction "B4_13") (pintype "passive"))
      (node (ref "S1") (pin "14") (pinfunction "B3_14") (pintype "passive"))
      (node (ref "S1") (pin "15") (pinfunction "B2_15") (pintype "passive"))
      (node (ref "S1") (pin "16") (pinfunction "B1_16") (pintype "passive"))
      (node (ref "S1") (pin "9") (pinfunction "B8_9") (pintype "passive"))
      (node (ref "S2") (pin "1") (pinfunction "1_1") (pintype "passive"))
      (node (ref "U10") (pin "12") (pinfunction "VSSA_12") (pintype "power_in"))
      (node (ref "U10") (pin "18") (pinfunction "VSS_4_18") (pintype "power_in"))
      (node (ref "U10") (pin "31") (pinfunction "VSS_1_31") (pintype "power_in"))
      (node (ref "U10") (pin "47") (pinfunction "VSS_2_47") (pintype "power_in"))
      (node (ref "U10") (pin "63") (pinfunction "VSS_3_63") (pintype "power_in"))
      (node (ref "U13") (pin "2") (pinfunction "K_2") (pintype "passive"))
      (node (ref "U14") (pin "2") (pinfunction "K_2") (pintype "passive"))
      (node (ref "U15") (pin "2") (pinfunction "K_2") (pintype "passive"))
      (node (ref "U16") (pin "3") (pinfunction "E_3") (pintype "passive"))
      (node (ref "U2") (pin "2") (pinfunction "IN-_2") (pintype "input"))
      (node (ref "U4") (pin "1") (pinfunction "Ground_1") (pintype "passive"))
      (node (ref "U5") (pin "9") (pinfunction "GND_9") (pintype "passive"))
      (node (ref "U7") (pin "1") (pinfunction "GND_1") (pintype "passive"))
      (node (ref "U8") (pin "10") (pinfunction "GND_10") (pintype "passive"))
      (node (ref "U8") (pin "12") (pinfunction "GND_12") (pintype "passive"))
      (node (ref "U8") (pin "5") (pinfunction "GND_5") (pintype "passive"))
    )
    (net (code "122") (name "unconnected-(P7-Pad6)") (class "Default")
      (node (ref "P7") (pin "6") (pinfunction "6_6") (pintype "passive+no_connect"))
    )
    (net (code "123") (name "unconnected-(P8-ANT-Pad1)") (class "Default")
      (node (ref "P8") (pin "1") (pinfunction "ANT_1") (pintype "passive+no_connect"))
    )
    (net (code "124") (name "unconnected-(P8-D3-Pad9)") (class "Default")
      (node (ref "P8") (pin "9") (pinfunction "D3_9") (pintype "passive+no_connect"))
    )
    (net (code "125") (name "unconnected-(P8-VT-Pad5)") (class "Default")
      (node (ref "P8") (pin "5") (pinfunction "VT_5") (pintype "passive+no_connect"))
    )
    (net (code "126") (name "unconnected-(U1-A-Pad3)") (class "Default")
      (node (ref "U1") (pin "3") (pinfunction "A_3") (pintype "passive+no_connect"))
    )
    (net (code "127") (name "unconnected-(U1-B-Pad4)") (class "Default")
      (node (ref "U1") (pin "4") (pinfunction "B_4") (pintype "passive+no_connect"))
    )
    (net (code "128") (name "unconnected-(U2-BYPASS-Pad7)") (class "Default")
      (node (ref "U2") (pin "7") (pinfunction "BYPASS_7") (pintype "passive+no_connect"))
    )
    (net (code "129") (name "unconnected-(U2-GAIN-Pad1)") (class "Default")
      (node (ref "U2") (pin "1") (pinfunction "GAIN_1") (pintype "passive+no_connect"))
    )
    (net (code "130") (name "unconnected-(U2-GAIN-Pad8)") (class "Default")
      (node (ref "U2") (pin "8") (pinfunction "GAIN_8") (pintype "passive+no_connect"))
    )
    (net (code "131") (name "unconnected-(U3-TAB-Pad6)") (class "Default")
      (node (ref "U3") (pin "6") (pinfunction "TAB_6") (pintype "power_in+no_connect"))
    )
    (net (code "132") (name "unconnected-(U5-ADC-Pad2)") (class "Default")
      (node (ref "U5") (pin "2") (pinfunction "ADC_2") (pintype "passive+no_connect"))
    )
    (net (code "133") (name "unconnected-(U5-GPIO0-Pad12)") (class "Default")
      (node (ref "U5") (pin "12") (pinfunction "GPIO0_12") (pintype "passive+no_connect"))
    )
    (net (code "134") (name "unconnected-(U5-GPIO2-Pad11)") (class "Default")
      (node (ref "U5") (pin "11") (pinfunction "GPIO2_11") (pintype "passive+no_connect"))
    )
    (net (code "135") (name "unconnected-(U5-GPIO4-Pad14)") (class "Default")
      (node (ref "U5") (pin "14") (pinfunction "GPIO4_14") (pintype "passive+no_connect"))
    )
    (net (code "136") (name "unconnected-(U5-GPIO5-Pad13)") (class "Default")
      (node (ref "U5") (pin "13") (pinfunction "GPIO5_13") (pintype "passive+no_connect"))
    )
    (net (code "137") (name "unconnected-(U5-GPIO12-Pad6)") (class "Default")
      (node (ref "U5") (pin "6") (pinfunction "GPIO12_6") (pintype "passive+no_connect"))
    )
    (net (code "138") (name "unconnected-(U5-GPIO13-Pad7)") (class "Default")
      (node (ref "U5") (pin "7") (pinfunction "GPIO13_7") (pintype "passive+no_connect"))
    )
    (net (code "139") (name "unconnected-(U5-GPIO14-Pad5)") (class "Default")
      (node (ref "U5") (pin "5") (pinfunction "GPIO14_5") (pintype "passive+no_connect"))
    )
    (net (code "140") (name "unconnected-(U5-GPIO16-Pad4)") (class "Default")
      (node (ref "U5") (pin "4") (pinfunction "GPIO16_4") (pintype "passive+no_connect"))
    )
    (net (code "141") (name "unconnected-(U8-INT1-Pad11)") (class "Default")
      (node (ref "U8") (pin "11") (pinfunction "INT1_11") (pintype "passive+no_connect"))
    )
    (net (code "142") (name "unconnected-(U8-INT2-Pad9)") (class "Default")
      (node (ref "U8") (pin "9") (pinfunction "INT2_9") (pintype "passive+no_connect"))
    )
    (net (code "143") (name "unconnected-(U8-NC-Pad3)") (class "Default")
      (node (ref "U8") (pin "3") (pinfunction "NC_3") (pintype "passive"))
    )
    (net (code "144") (name "unconnected-(U8-NC-Pad8)") (class "Default")
      (node (ref "U8") (pin "8") (pinfunction "NC_8") (pintype "passive"))
    )
    (net (code "145") (name "unconnected-(U8-NC-Pad13)") (class "Default")
      (node (ref "U8") (pin "13") (pinfunction "NC_13") (pintype "passive"))
    )
    (net (code "146") (name "unconnected-(U8-NC-Pad15)") (class "Default")
      (node (ref "U8") (pin "15") (pinfunction "NC_15") (pintype "passive"))
    )
    (net (code "147") (name "unconnected-(U8-NC-Pad16)") (class "Default")
      (node (ref "U8") (pin "16") (pinfunction "NC_16") (pintype "passive"))
    )
    (net (code "148") (name "unconnected-(U10A-PA8-Pad41)") (class "Default")
      (node (ref "U10") (pin "41") (pinfunction "PA8_41") (pintype "bidirectional+no_connect"))
    )
    (net (code "149") (name "unconnected-(U10A-PA15-Pad50)") (class "Default")
      (node (ref "U10") (pin "50") (pinfunction "PA15_50") (pintype "bidirectional+no_connect"))
    )
    (net (code "150") (name "unconnected-(U10A-PB3-Pad55)") (class "Default")
      (node (ref "U10") (pin "55") (pinfunction "PB3_55") (pintype "bidirectional+no_connect"))
    )
    (net (code "151") (name "unconnected-(U10A-PC13-TAMPER-RTC-Pad2)") (class "Default")
      (node (ref "U10") (pin "2") (pinfunction "PC13-TAMPER-RTC_2") (pintype "bidirectional+no_connect"))
    )
    (net (code "152") (name "unconnected-(U10A-PC14-OSC32_IN-Pad3)") (class "Default")
      (node (ref "U10") (pin "3") (pinfunction "PC14-OSC32_IN_3") (pintype "bidirectional+no_connect"))
    )
    (net (code "153") (name "unconnected-(U10A-PC15-OSC32_OUT-Pad4)") (class "Default")
      (node (ref "U10") (pin "4") (pinfunction "PC15-OSC32_OUT_4") (pintype "bidirectional+no_connect"))
    )
    (net (code "154") (name "unconnected-(U10B-VBAT-Pad1)") (class "Default")
      (node (ref "U10") (pin "1") (pinfunction "VBAT_1") (pintype "power_in+no_connect"))
    )
  )
)
